# shield.net
KiCad netlist of a schematic drawn in EAGLE
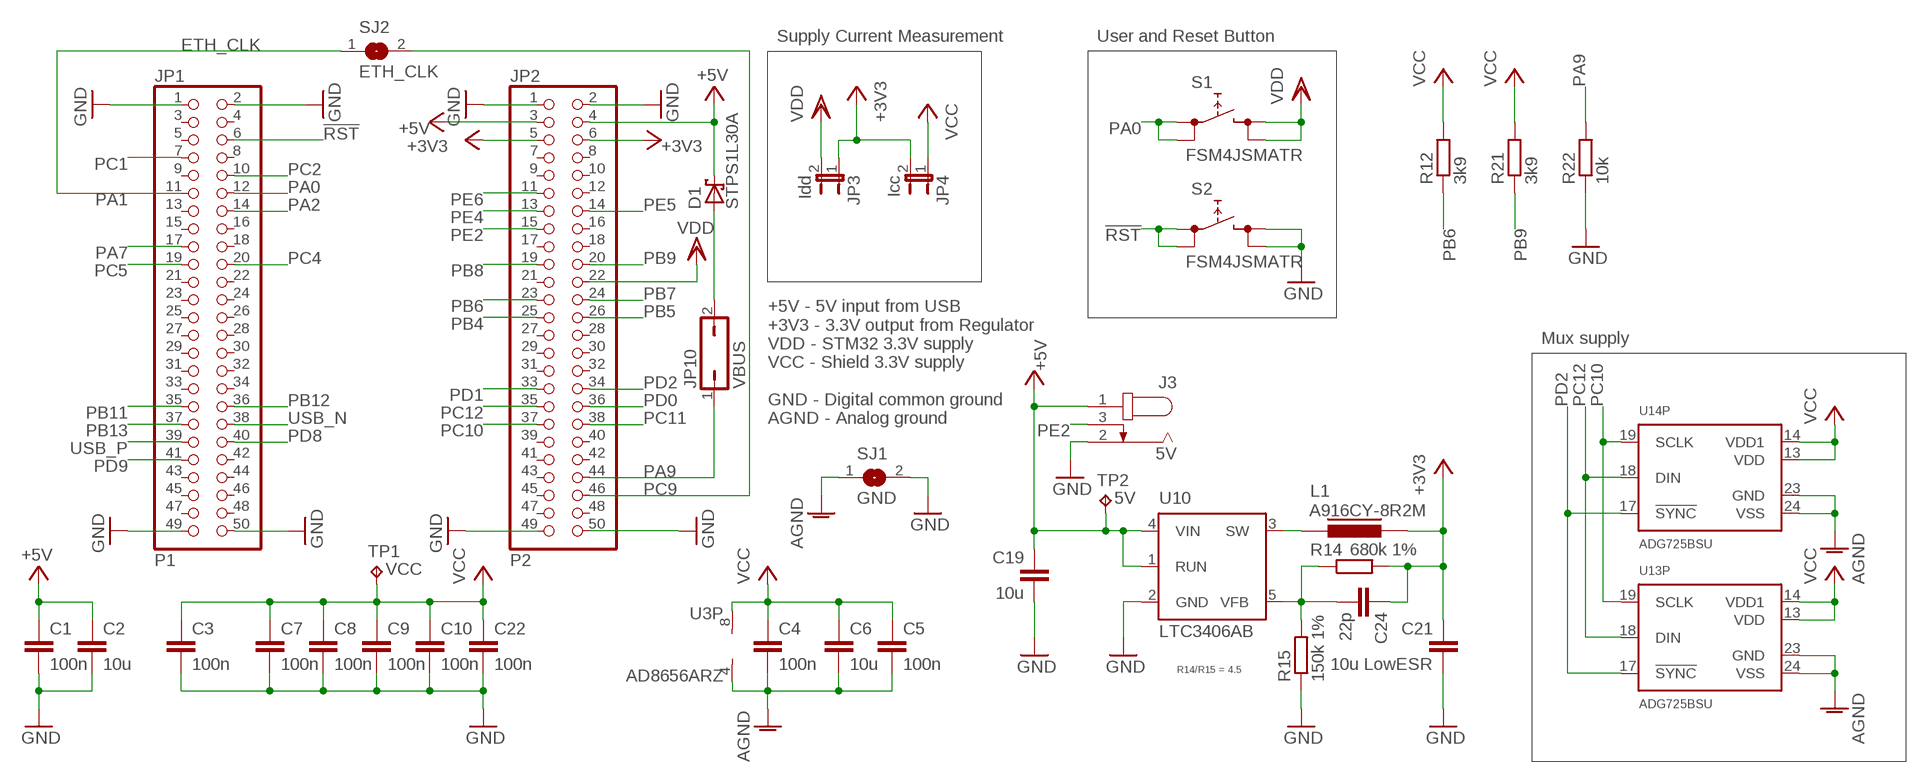
[diagram p0: schematic, sheet 1]
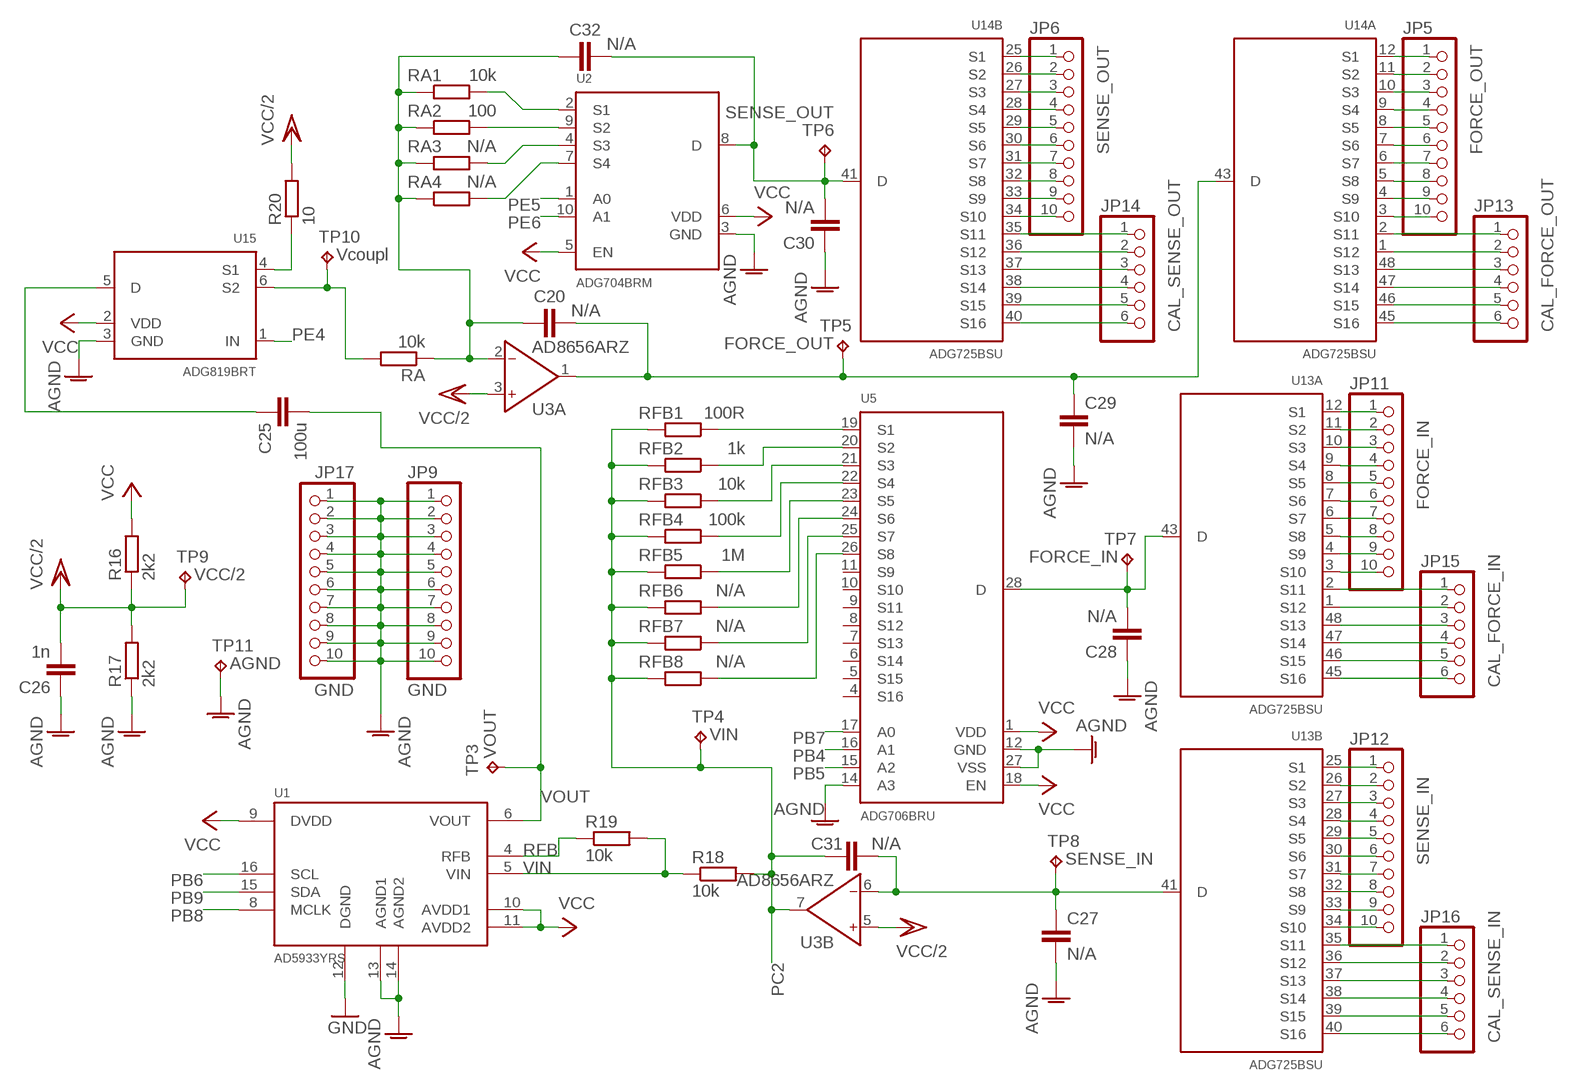
[diagram p1: schematic, sheet 2]
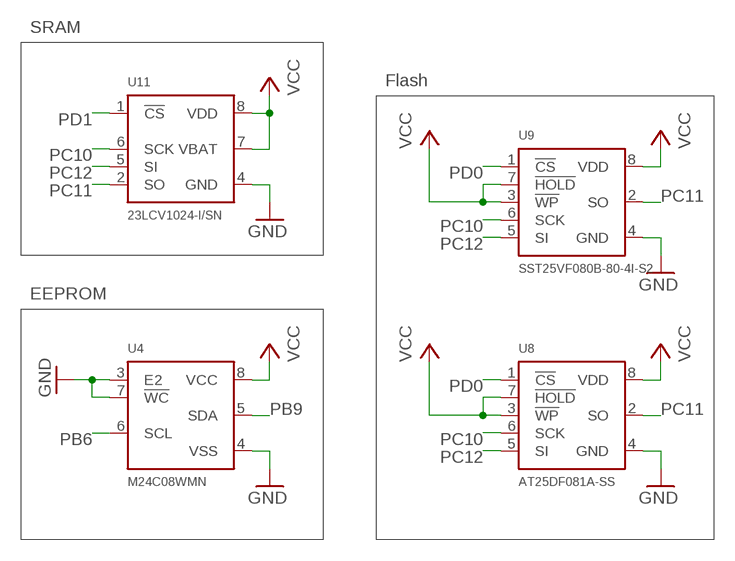
[diagram p2: schematic, sheet 3]
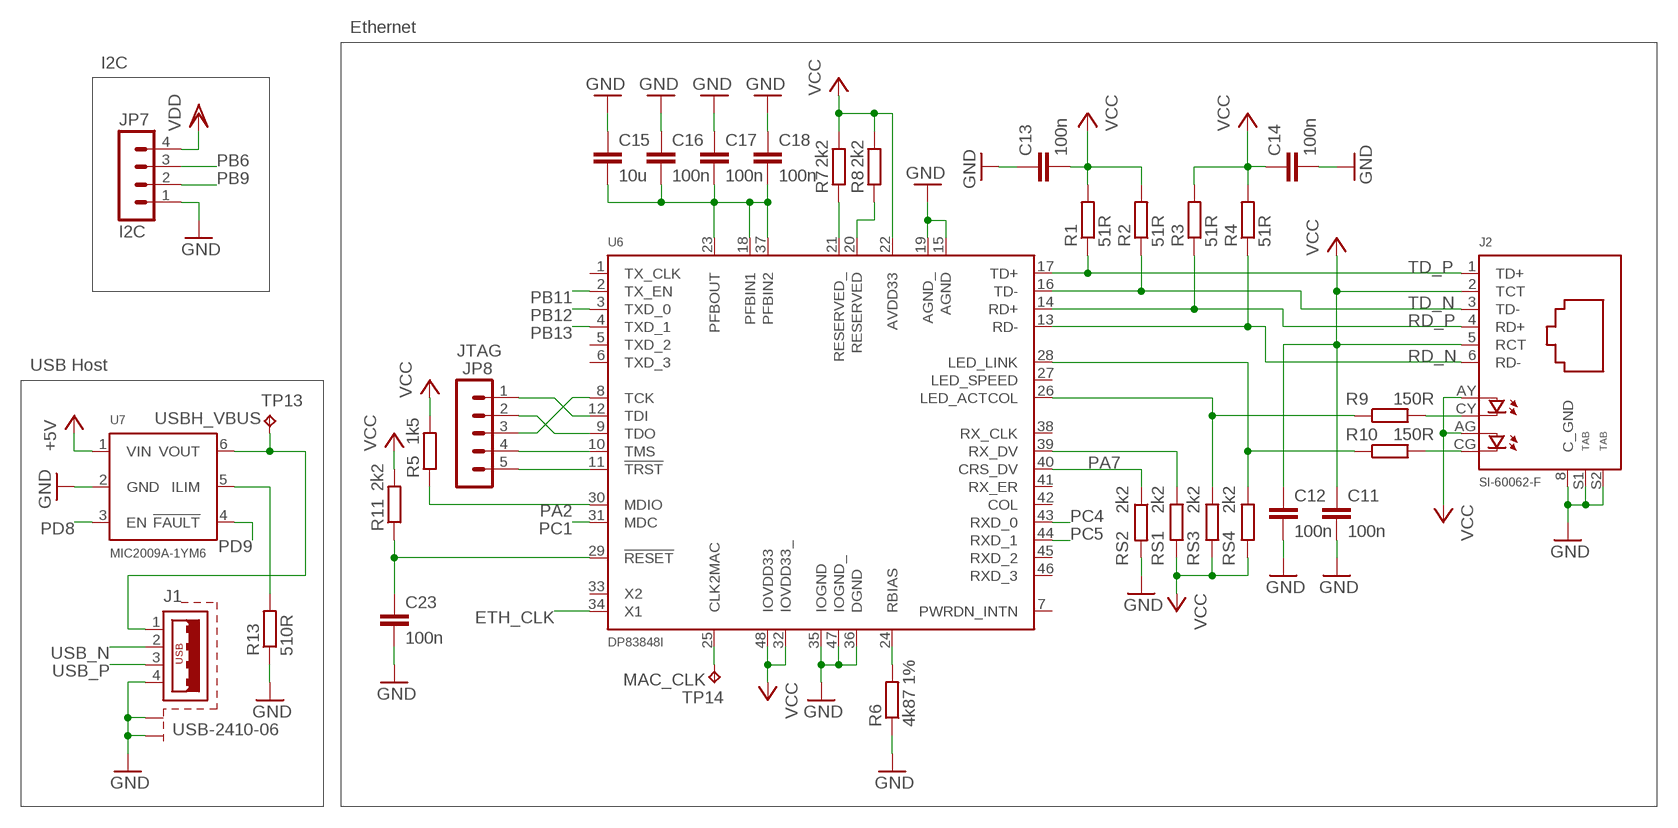
[diagram p3: schematic, sheet 4]

(export (version "E")
  (design (tool "Eeschema 10.0.6"))
  (components
    (comp (ref "U4")
      (value "M24C08WMN")
      (footprint "eagle-import:SO8")
      (libsource (lib "eagle-import") (part "M24C08MNW"))
    )
    (comp (ref "U8")
      (value "AT25DF081A-SS")
      (footprint "eagle-import:SO8")
      (libsource (lib "eagle-import") (part "AT25DF081A-SS"))
    )
    (comp (ref "U9")
      (value "SST25VF080B-80-4I-S2")
      (footprint "eagle-import:SOIC8")
      (libsource (lib "eagle-import") (part "SST25VF080B-S2-80-4I"))
    )
    (comp (ref "U11")
      (value "23LCV1024-I/SN")
      (footprint "eagle-import:SO8")
      (libsource (lib "eagle-import") (part "23LCV1024/SN-I"))
    )
    (comp (ref "C11")
      (value "100n")
      (footprint "eagle-import:C0603")
      (libsource (lib "eagle-import") (part "C-EUC0603"))
    )
    (comp (ref "C12")
      (value "100n")
      (footprint "eagle-import:C0603")
      (libsource (lib "eagle-import") (part "C-EUC0603"))
    )
    (comp (ref "C13")
      (value "100n")
      (footprint "eagle-import:C0603")
      (libsource (lib "eagle-import") (part "C-EUC0603"))
    )
    (comp (ref "C14")
      (value "100n")
      (footprint "eagle-import:C0603")
      (libsource (lib "eagle-import") (part "C-EUC0603"))
    )
    (comp (ref "C15")
      (value "10u")
      (footprint "eagle-import:C0603")
      (libsource (lib "eagle-import") (part "C-EUC0603"))
    )
    (comp (ref "C16")
      (value "100n")
      (footprint "eagle-import:C0603")
      (libsource (lib "eagle-import") (part "C-EUC0603"))
    )
    (comp (ref "C17")
      (value "100n")
      (footprint "eagle-import:C0603")
      (libsource (lib "eagle-import") (part "C-EUC0603"))
    )
    (comp (ref "C18")
      (value "100n")
      (footprint "eagle-import:C0603")
      (libsource (lib "eagle-import") (part "C-EUC0603"))
    )
    (comp (ref "C23")
      (value "100n")
      (footprint "eagle-import:C0603")
      (libsource (lib "eagle-import") (part "C-EUC0603"))
    )
    (comp (ref "J1")
      (value "USB-2410-06")
      (footprint "eagle-import:USB-2410-06")
      (libsource (lib "eagle-import") (part "USB-2410-06"))
    )
    (comp (ref "J2")
      (value "SI-60062-F")
      (footprint "eagle-import:SI-60062-F")
      (libsource (lib "eagle-import") (part "SI-60062-F"))
    )
    (comp (ref "JP7")
      (value "I2C")
      (footprint "eagle-import:MA04-1")
      (libsource (lib "eagle-import") (part "MA04-1"))
    )
    (comp (ref "JP8")
      (value "JTAG")
      (footprint "eagle-import:MA05-1")
      (libsource (lib "eagle-import") (part "MA05-1"))
    )
    (comp (ref "R1")
      (value "51R")
      (footprint "eagle-import:R0603")
      (libsource (lib "eagle-import") (part "R-EU_R0603"))
    )
    (comp (ref "R2")
      (value "51R")
      (footprint "eagle-import:R0603")
      (libsource (lib "eagle-import") (part "R-EU_R0603"))
    )
    (comp (ref "R3")
      (value "51R")
      (footprint "eagle-import:R0603")
      (libsource (lib "eagle-import") (part "R-EU_R0603"))
    )
    (comp (ref "R4")
      (value "51R")
      (footprint "eagle-import:R0603")
      (libsource (lib "eagle-import") (part "R-EU_R0603"))
    )
    (comp (ref "R5")
      (value "1k5")
      (footprint "eagle-import:R0603")
      (libsource (lib "eagle-import") (part "R-EU_R0603"))
    )
    (comp (ref "R6")
      (value "4k87 1%")
      (footprint "eagle-import:R0603")
      (libsource (lib "eagle-import") (part "R-EU_R0603"))
    )
    (comp (ref "R7")
      (value "2k2")
      (footprint "eagle-import:R0603")
      (libsource (lib "eagle-import") (part "R-EU_R0603"))
    )
    (comp (ref "R8")
      (value "2k2")
      (footprint "eagle-import:R0603")
      (libsource (lib "eagle-import") (part "R-EU_R0603"))
    )
    (comp (ref "R9")
      (value "150R")
      (footprint "eagle-import:R0603")
      (libsource (lib "eagle-import") (part "R-EU_R0603"))
    )
    (comp (ref "R10")
      (value "150R")
      (footprint "eagle-import:R0603")
      (libsource (lib "eagle-import") (part "R-EU_R0603"))
    )
    (comp (ref "R11")
      (value "2k2")
      (footprint "eagle-import:R0603")
      (libsource (lib "eagle-import") (part "R-EU_R0603"))
    )
    (comp (ref "R13")
      (value "510R")
      (footprint "eagle-import:R0603")
      (libsource (lib "eagle-import") (part "R-EU_R0603"))
    )
    (comp (ref "RS1")
      (value "2k2")
      (footprint "eagle-import:R0603")
      (libsource (lib "eagle-import") (part "R-EU_R0603"))
    )
    (comp (ref "RS2")
      (value "2k2")
      (footprint "eagle-import:R0603")
      (libsource (lib "eagle-import") (part "R-EU_R0603"))
    )
    (comp (ref "RS3")
      (value "2k2")
      (footprint "eagle-import:R0603")
      (libsource (lib "eagle-import") (part "R-EU_R0603"))
    )
    (comp (ref "RS4")
      (value "2k2")
      (footprint "eagle-import:R0603")
      (libsource (lib "eagle-import") (part "R-EU_R0603"))
    )
    (comp (ref "TP13")
      (value "TPTP20R")
      (footprint "eagle-import:TP20R")
      (fields (field (name "TP_SIGNAL_NAME") "USBH_VBUS"))
      (libsource (lib "eagle-import") (part "TPTP20R"))
    )
    (comp (ref "TP14")
      (value "TPTP20R")
      (footprint "eagle-import:TP20R")
      (fields (field (name "TP_SIGNAL_NAME") "MAC_CLK"))
      (libsource (lib "eagle-import") (part "TPTP20R"))
    )
    (comp (ref "U6")
      (value "DP83848I")
      (footprint "eagle-import:LQFP48")
      (fields (field (name "MPN") "DP83848IVV"))
      (libsource (lib "eagle-import") (part "DP83848I"))
    )
    (comp (ref "U7")
      (value "MIC2009A-1YM6")
      (footprint "eagle-import:SOT23-6")
      (libsource (lib "eagle-import") (part "MIC2009A-1YM6"))
    )
    (comp (ref "C20")
      (value "N/A")
      (footprint "eagle-import:C0603")
      (libsource (lib "eagle-import") (part "C-EUC0603"))
    )
    (comp (ref "C25")
      (value "100u")
      (footprint "eagle-import:C1206")
      (libsource (lib "eagle-import") (part "C-EUC1206"))
    )
    (comp (ref "C26")
      (value "1n")
      (footprint "eagle-import:C0603")
      (libsource (lib "eagle-import") (part "C-EUC0603"))
    )
    (comp (ref "C27")
      (value "N/A")
      (footprint "eagle-import:C0805")
      (libsource (lib "eagle-import") (part "C-EUC0805"))
    )
    (comp (ref "C28")
      (value "N/A")
      (footprint "eagle-import:C0805")
      (libsource (lib "eagle-import") (part "C-EUC0805"))
    )
    (comp (ref "C29")
      (value "N/A")
      (footprint "eagle-import:C0805")
      (libsource (lib "eagle-import") (part "C-EUC0805"))
    )
    (comp (ref "C30")
      (value "N/A")
      (footprint "eagle-import:C0805")
      (libsource (lib "eagle-import") (part "C-EUC0805"))
    )
    (comp (ref "C31")
      (value "N/A")
      (footprint "eagle-import:C0603")
      (libsource (lib "eagle-import") (part "C-EUC0603"))
    )
    (comp (ref "C32")
      (value "N/A")
      (footprint "eagle-import:C0603")
      (libsource (lib "eagle-import") (part "C-EUC0603"))
    )
    (comp (ref "JP5")
      (value "FORCE_OUT")
      (footprint "eagle-import:1X10")
      (libsource (lib "eagle-import") (part "PINHD-1X10"))
    )
    (comp (ref "JP6")
      (value "SENSE_OUT")
      (footprint "eagle-import:1X10")
      (libsource (lib "eagle-import") (part "PINHD-1X10"))
    )
    (comp (ref "JP9")
      (value "GND")
      (footprint "eagle-import:1X10")
      (libsource (lib "eagle-import") (part "PINHD-1X10"))
    )
    (comp (ref "JP11")
      (value "FORCE_IN")
      (footprint "eagle-import:1X10")
      (libsource (lib "eagle-import") (part "PINHD-1X10"))
    )
    (comp (ref "JP12")
      (value "SENSE_IN")
      (footprint "eagle-import:1X10")
      (libsource (lib "eagle-import") (part "PINHD-1X10"))
    )
    (comp (ref "JP13")
      (value "CAL_FORCE_OUT")
      (footprint "eagle-import:1X06")
      (libsource (lib "eagle-import") (part "PINHD-1X6"))
    )
    (comp (ref "JP14")
      (value "CAL_SENSE_OUT")
      (footprint "eagle-import:1X06")
      (libsource (lib "eagle-import") (part "PINHD-1X6"))
    )
    (comp (ref "JP15")
      (value "CAL_FORCE_IN")
      (footprint "eagle-import:1X06")
      (libsource (lib "eagle-import") (part "PINHD-1X6"))
    )
    (comp (ref "JP16")
      (value "CAL_SENSE_IN")
      (footprint "eagle-import:1X06")
      (libsource (lib "eagle-import") (part "PINHD-1X6"))
    )
    (comp (ref "JP17")
      (value "GND")
      (footprint "eagle-import:1X10")
      (libsource (lib "eagle-import") (part "PINHD-1X10"))
    )
    (comp (ref "R16")
      (value "2k2")
      (footprint "eagle-import:R0603")
      (libsource (lib "eagle-import") (part "R-EU_R0603"))
    )
    (comp (ref "R17")
      (value "2k2")
      (footprint "eagle-import:R0603")
      (libsource (lib "eagle-import") (part "R-EU_R0603"))
    )
    (comp (ref "R18")
      (value "10k")
      (footprint "eagle-import:R0603")
      (libsource (lib "eagle-import") (part "R-EU_R0603"))
    )
    (comp (ref "R19")
      (value "10k")
      (footprint "eagle-import:R0603")
      (libsource (lib "eagle-import") (part "R-EU_R0603"))
    )
    (comp (ref "R20")
      (value "10")
      (footprint "eagle-import:R0603")
      (libsource (lib "eagle-import") (part "R-EU_R0603"))
    )
    (comp (ref "RA")
      (value "10k")
      (footprint "eagle-import:R0603")
      (libsource (lib "eagle-import") (part "R-EU_R0603"))
    )
    (comp (ref "RA1")
      (value "10k")
      (footprint "eagle-import:R0603")
      (libsource (lib "eagle-import") (part "R-EU_R0603"))
    )
    (comp (ref "RA2")
      (value "100")
      (footprint "eagle-import:R0603")
      (libsource (lib "eagle-import") (part "R-EU_R0603"))
    )
    (comp (ref "RA3")
      (value "N/A")
      (footprint "eagle-import:R0603")
      (libsource (lib "eagle-import") (part "R-EU_R0603"))
    )
    (comp (ref "RA4")
      (value "N/A")
      (footprint "eagle-import:R0603")
      (libsource (lib "eagle-import") (part "R-EU_R0603"))
    )
    (comp (ref "RFB1")
      (value "100R")
      (footprint "eagle-import:R0603")
      (libsource (lib "eagle-import") (part "R-EU_R0603"))
    )
    (comp (ref "RFB2")
      (value "1k")
      (footprint "eagle-import:R0603")
      (libsource (lib "eagle-import") (part "R-EU_R0603"))
    )
    (comp (ref "RFB3")
      (value "10k")
      (footprint "eagle-import:R0603")
      (libsource (lib "eagle-import") (part "R-EU_R0603"))
    )
    (comp (ref "RFB4")
      (value "100k")
      (footprint "eagle-import:R0603")
      (libsource (lib "eagle-import") (part "R-EU_R0603"))
    )
    (comp (ref "RFB5")
      (value "1M")
      (footprint "eagle-import:R0603")
      (libsource (lib "eagle-import") (part "R-EU_R0603"))
    )
    (comp (ref "RFB6")
      (value "N/A")
      (footprint "eagle-import:R0603")
      (libsource (lib "eagle-import") (part "R-EU_R0603"))
    )
    (comp (ref "RFB7")
      (value "N/A")
      (footprint "eagle-import:R0603")
      (libsource (lib "eagle-import") (part "R-EU_R0603"))
    )
    (comp (ref "RFB8")
      (value "N/A")
      (footprint "eagle-import:R0603")
      (libsource (lib "eagle-import") (part "R-EU_R0603"))
    )
    (comp (ref "TP3")
      (value "TPTP20R")
      (footprint "eagle-import:TP20R")
      (fields (field (name "TP_SIGNAL_NAME") "VOUT"))
      (libsource (lib "eagle-import") (part "TPTP20R"))
    )
    (comp (ref "TP4")
      (value "TPTP20R")
      (footprint "eagle-import:TP20R")
      (fields (field (name "TP_SIGNAL_NAME") "VIN"))
      (libsource (lib "eagle-import") (part "TPTP20R"))
    )
    (comp (ref "TP5")
      (value "TPTP20R")
      (footprint "eagle-import:TP20R")
      (fields (field (name "TP_SIGNAL_NAME") "FORCE_OUT"))
      (libsource (lib "eagle-import") (part "TPTP20R"))
    )
    (comp (ref "TP6")
      (value "TPTP20R")
      (footprint "eagle-import:TP20R")
      (fields (field (name "TP_SIGNAL_NAME") "SENSE_OUT"))
      (libsource (lib "eagle-import") (part "TPTP20R"))
    )
    (comp (ref "TP7")
      (value "TPTP20R")
      (footprint "eagle-import:TP20R")
      (fields (field (name "TP_SIGNAL_NAME") "FORCE_IN"))
      (libsource (lib "eagle-import") (part "TPTP20R"))
    )
    (comp (ref "TP8")
      (value "TPTP20R")
      (footprint "eagle-import:TP20R")
      (fields (field (name "TP_SIGNAL_NAME") "SENSE_IN"))
      (libsource (lib "eagle-import") (part "TPTP20R"))
    )
    (comp (ref "TP9")
      (value "TPTP20R")
      (footprint "eagle-import:TP20R")
      (fields (field (name "TP_SIGNAL_NAME") "VCC/2"))
      (libsource (lib "eagle-import") (part "TPTP20R"))
    )
    (comp (ref "TP10")
      (value "TPTP20R")
      (footprint "eagle-import:TP20R")
      (fields (field (name "TP_SIGNAL_NAME") "Vcoupl"))
      (libsource (lib "eagle-import") (part "TPTP20R"))
    )
    (comp (ref "TP11")
      (value "TPPAD1-13")
      (footprint "eagle-import:P1-13")
      (fields (field (name "TP_SIGNAL_NAME") "AGND"))
      (libsource (lib "eagle-import") (part "TPPAD1-13"))
    )
    (comp (ref "U1")
      (value "AD5933YRS")
      (footprint "eagle-import:SSOP16")
      (libsource (lib "eagle-import") (part "AD5933RSY"))
    )
    (comp (ref "U2")
      (value "ADG704BRM")
      (footprint "eagle-import:MSOP10")
      (libsource (lib "eagle-import") (part "ADG704RMB"))
    )
    (comp (ref "U3")
      (value "AD8656ARZ")
      (footprint "eagle-import:SOIC8")
      (libsource (lib "eagle-import") (part "AD8656ZAR"))
    )
    (comp (ref "U5")
      (value "ADG706BRU")
      (footprint "eagle-import:TSSOP28")
      (libsource (lib "eagle-import") (part "ADG706RUB"))
    )
    (comp (ref "U13")
      (value "ADG725BSU")
      (footprint "eagle-import:TQFP48")
      (libsource (lib "eagle-import") (part "ADG725SUB"))
    )
    (comp (ref "U14")
      (value "ADG725BSU")
      (footprint "eagle-import:TQFP48")
      (libsource (lib "eagle-import") (part "ADG725SUB"))
    )
    (comp (ref "U15")
      (value "ADG819BRT")
      (footprint "eagle-import:SOT23-6")
      (libsource (lib "eagle-import") (part "ADG819RTB"))
    )
    (comp (ref "C1")
      (value "100n")
      (footprint "eagle-import:C0603")
      (libsource (lib "eagle-import") (part "C-EUC0603"))
    )
    (comp (ref "C2")
      (value "10u")
      (footprint "eagle-import:C0603")
      (libsource (lib "eagle-import") (part "C-EUC0603"))
    )
    (comp (ref "C3")
      (value "100n")
      (footprint "eagle-import:C0603")
      (libsource (lib "eagle-import") (part "C-EUC0603"))
    )
    (comp (ref "C4")
      (value "100n")
      (footprint "eagle-import:C0603")
      (libsource (lib "eagle-import") (part "C-EUC0603"))
    )
    (comp (ref "C5")
      (value "100n")
      (footprint "eagle-import:C0603")
      (libsource (lib "eagle-import") (part "C-EUC0603"))
    )
    (comp (ref "C6")
      (value "10u")
      (footprint "eagle-import:C0603")
      (libsource (lib "eagle-import") (part "C-EUC0603"))
    )
    (comp (ref "C7")
      (value "100n")
      (footprint "eagle-import:C0603")
      (libsource (lib "eagle-import") (part "C-EUC0603"))
    )
    (comp (ref "C8")
      (value "100n")
      (footprint "eagle-import:C0603")
      (libsource (lib "eagle-import") (part "C-EUC0603"))
    )
    (comp (ref "C9")
      (value "100n")
      (footprint "eagle-import:C0603")
      (libsource (lib "eagle-import") (part "C-EUC0603"))
    )
    (comp (ref "C10")
      (value "100n")
      (footprint "eagle-import:C0603")
      (libsource (lib "eagle-import") (part "C-EUC0603"))
    )
    (comp (ref "C19")
      (value "10u")
      (footprint "eagle-import:C3216")
      (libsource (lib "eagle-import") (part "C-EUC3216"))
    )
    (comp (ref "C21")
      (value "10u LowESR")
      (footprint "eagle-import:C3216")
      (libsource (lib "eagle-import") (part "C-EUC3216"))
    )
    (comp (ref "C22")
      (value "100n")
      (footprint "eagle-import:C0603")
      (libsource (lib "eagle-import") (part "C-EUC0603"))
    )
    (comp (ref "C24")
      (value "22p")
      (footprint "eagle-import:C0603")
      (libsource (lib "eagle-import") (part "C-EUC0603"))
    )
    (comp (ref "D1")
      (value "STPS1L30A")
      (footprint "eagle-import:DO214AC")
      (libsource (lib "eagle-import") (part "STPS1L30A"))
    )
    (comp (ref "J3")
      (value "5V")
      (footprint "eagle-import:JACK-SMD2.5")
      (libsource (lib "eagle-import") (part "JACK-PLUG-S2.5"))
    )
    (comp (ref "JP1")
      (value "P1")
      (footprint "eagle-import:2X25-F")
      (libsource (lib "eagle-import") (part "PINHD-2X25-F"))
    )
    (comp (ref "JP2")
      (value "P2")
      (footprint "eagle-import:2X25-F")
      (libsource (lib "eagle-import") (part "PINHD-2X25-F"))
    )
    (comp (ref "JP3")
      (value "Idd")
      (footprint "eagle-import:JP1")
      (libsource (lib "eagle-import") (part "JP1E"))
    )
    (comp (ref "JP4")
      (value "Icc")
      (footprint "eagle-import:JP1")
      (libsource (lib "eagle-import") (part "JP1E"))
    )
    (comp (ref "JP10")
      (value "VBUS")
      (footprint "eagle-import:JP1")
      (libsource (lib "eagle-import") (part "JP1Q"))
    )
    (comp (ref "L1")
      (value "A916CY-8R2M")
      (footprint "eagle-import:D63CB")
      (libsource (lib "eagle-import") (part "A916CY-8R2M"))
    )
    (comp (ref "R12")
      (value "3k9")
      (footprint "eagle-import:R0603")
      (libsource (lib "eagle-import") (part "R-EU_R0603"))
    )
    (comp (ref "R14")
      (value "680k 1%")
      (footprint "eagle-import:R0603")
      (libsource (lib "eagle-import") (part "R-EU_R0603"))
    )
    (comp (ref "R15")
      (value "150k 1%")
      (footprint "eagle-import:R0603")
      (libsource (lib "eagle-import") (part "R-EU_R0603"))
    )
    (comp (ref "R21")
      (value "3k9")
      (footprint "eagle-import:R0603")
      (libsource (lib "eagle-import") (part "R-EU_R0603"))
    )
    (comp (ref "R22")
      (value "10k")
      (footprint "eagle-import:R0603")
      (libsource (lib "eagle-import") (part "R-EU_R0603"))
    )
    (comp (ref "S1")
      (value "FSM4JSMATR")
      (footprint "eagle-import:FSM")
      (libsource (lib "eagle-import") (part "FSM4JSMATR"))
    )
    (comp (ref "S2")
      (value "FSM4JSMATR")
      (footprint "eagle-import:FSM")
      (libsource (lib "eagle-import") (part "FSM4JSMATR"))
    )
    (comp (ref "SJ1")
      (value "GND")
      (footprint "eagle-import:SJ")
      (libsource (lib "eagle-import") (part "SJ"))
    )
    (comp (ref "SJ2")
      (value "ETH_CLK")
      (footprint "eagle-import:SJ")
      (libsource (lib "eagle-import") (part "SJ"))
    )
    (comp (ref "TP1")
      (value "TPTP20R")
      (footprint "eagle-import:TP20R")
      (fields (field (name "TP_SIGNAL_NAME") "VCC"))
      (libsource (lib "eagle-import") (part "TPTP20R"))
    )
    (comp (ref "TP2")
      (value "TPTP20R")
      (footprint "eagle-import:TP20R")
      (fields (field (name "TP_SIGNAL_NAME") "5V"))
      (libsource (lib "eagle-import") (part "TPTP20R"))
    )
    (comp (ref "U10")
      (value "LTC3406AB")
      (footprint "eagle-import:TSOT23-5")
      (libsource (lib "eagle-import") (part "LTC3406AB"))
    )
  )
  (nets
    (net (code "1") (name "+3V3") (class "Default")
      (node (ref "C21") (pin "1") (pinfunction "1_1") (pintype "passive"))
      (node (ref "C24") (pin "1") (pinfunction "1_1") (pintype "passive"))
      (node (ref "JP2") (pin "5") (pinfunction "5_5") (pintype "passive"))
      (node (ref "JP2") (pin "6") (pinfunction "6_6") (pintype "passive"))
      (node (ref "JP3") (pin "1") (pinfunction "1_1") (pintype "passive"))
      (node (ref "JP4") (pin "2") (pinfunction "2_2") (pintype "passive"))
      (node (ref "L1") (pin "2") (pinfunction "2_2") (pintype "passive"))
      (node (ref "R14") (pin "2") (pinfunction "2_2") (pintype "passive"))
    )
    (net (code "2") (name "+5V") (class "Default")
      (node (ref "C1") (pin "1") (pinfunction "1_1") (pintype "passive"))
      (node (ref "C19") (pin "1") (pinfunction "1_1") (pintype "passive"))
      (node (ref "C2") (pin "1") (pinfunction "1_1") (pintype "passive"))
      (node (ref "D1") (pin "C") (pinfunction "C_C") (pintype "passive"))
      (node (ref "J3") (pin "1") (pinfunction "1_1") (pintype "passive"))
      (node (ref "JP2") (pin "3") (pinfunction "3_3") (pintype "passive"))
      (node (ref "JP2") (pin "4") (pinfunction "4_4") (pintype "passive"))
      (node (ref "TP2") (pin "TP") (pinfunction "TP_TP") (pintype "input"))
      (node (ref "U10") (pin "1") (pinfunction "RUN_1") (pintype "input"))
      (node (ref "U10") (pin "4") (pinfunction "VIN_4") (pintype "power_in"))
      (node (ref "U7") (pin "1") (pinfunction "VIN_1") (pintype "power_in"))
    )
    (net (code "3") (name "AGND") (class "Default")
      (node (ref "C26") (pin "1") (pinfunction "1_1") (pintype "passive"))
      (node (ref "C27") (pin "2") (pinfunction "2_2") (pintype "passive"))
      (node (ref "C28") (pin "1") (pinfunction "1_1") (pintype "passive"))
      (node (ref "C29") (pin "2") (pinfunction "2_2") (pintype "passive"))
      (node (ref "C30") (pin "1") (pinfunction "1_1") (pintype "passive"))
      (node (ref "C4") (pin "2") (pinfunction "2_2") (pintype "passive"))
      (node (ref "C5") (pin "2") (pinfunction "2_2") (pintype "passive"))
      (node (ref "C6") (pin "2") (pinfunction "2_2") (pintype "passive"))
      (node (ref "JP17") (pin "1") (pinfunction "1_1") (pintype "passive"))
      (node (ref "JP17") (pin "10") (pinfunction "10_10") (pintype "passive"))
      (node (ref "JP17") (pin "2") (pinfunction "2_2") (pintype "passive"))
      (node (ref "JP17") (pin "3") (pinfunction "3_3") (pintype "passive"))
      (node (ref "JP17") (pin "4") (pinfunction "4_4") (pintype "passive"))
      (node (ref "JP17") (pin "5") (pinfunction "5_5") (pintype "passive"))
      (node (ref "JP17") (pin "6") (pinfunction "6_6") (pintype "passive"))
      (node (ref "JP17") (pin "7") (pinfunction "7_7") (pintype "passive"))
      (node (ref "JP17") (pin "8") (pinfunction "8_8") (pintype "passive"))
      (node (ref "JP17") (pin "9") (pinfunction "9_9") (pintype "passive"))
      (node (ref "JP9") (pin "1") (pinfunction "1_1") (pintype "passive"))
      (node (ref "JP9") (pin "10") (pinfunction "10_10") (pintype "passive"))
      (node (ref "JP9") (pin "2") (pinfunction "2_2") (pintype "passive"))
      (node (ref "JP9") (pin "3") (pinfunction "3_3") (pintype "passive"))
      (node (ref "JP9") (pin "4") (pinfunction "4_4") (pintype "passive"))
      (node (ref "JP9") (pin "5") (pinfunction "5_5") (pintype "passive"))
      (node (ref "JP9") (pin "6") (pinfunction "6_6") (pintype "passive"))
      (node (ref "JP9") (pin "7") (pinfunction "7_7") (pintype "passive"))
      (node (ref "JP9") (pin "8") (pinfunction "8_8") (pintype "passive"))
      (node (ref "JP9") (pin "9") (pinfunction "9_9") (pintype "passive"))
      (node (ref "R17") (pin "1") (pinfunction "1_1") (pintype "passive"))
      (node (ref "SJ1") (pin "1") (pinfunction "1_1") (pintype "passive"))
      (node (ref "TP11") (pin "TP") (pinfunction "TP_TP") (pintype "input"))
      (node (ref "U1") (pin "13") (pinfunction "AGND1_13") (pintype "bidirectional"))
      (node (ref "U1") (pin "14") (pinfunction "AGND2_14") (pintype "bidirectional"))
      (node (ref "U13") (pin "23") (pinfunction "GND_23") (pintype "power_in"))
      (node (ref "U13") (pin "24") (pinfunction "VSS_24") (pintype "power_in"))
      (node (ref "U14") (pin "23") (pinfunction "GND_23") (pintype "power_in"))
      (node (ref "U14") (pin "24") (pinfunction "VSS_24") (pintype "power_in"))
      (node (ref "U15") (pin "3") (pinfunction "GND_3") (pintype "power_in"))
      (node (ref "U2") (pin "3") (pinfunction "GND_3") (pintype "power_in"))
      (node (ref "U3") (pin "4") (pinfunction "V-_4") (pintype "power_in"))
      (node (ref "U5") (pin "12") (pinfunction "GND_12") (pintype "power_in"))
      (node (ref "U5") (pin "14") (pinfunction "A3_14") (pintype "input"))
      (node (ref "U5") (pin "27") (pinfunction "VSS_27") (pintype "power_in"))
    )
    (net (code "4") (name "ETH_CLK") (class "Default")
      (node (ref "JP1") (pin "11") (pinfunction "11_11") (pintype "passive"))
      (node (ref "SJ2") (pin "1") (pinfunction "1_1") (pintype "passive"))
      (node (ref "U6") (pin "34") (pinfunction "X1_34") (pintype "input"))
    )
    (net (code "5") (name "GND") (class "Default")
      (node (ref "C1") (pin "2") (pinfunction "2_2") (pintype "passive"))
      (node (ref "C10") (pin "2") (pinfunction "2_2") (pintype "passive"))
      (node (ref "C11") (pin "2") (pinfunction "2_2") (pintype "passive"))
      (node (ref "C12") (pin "2") (pinfunction "2_2") (pintype "passive"))
      (node (ref "C13") (pin "1") (pinfunction "1_1") (pintype "passive"))
      (node (ref "C14") (pin "2") (pinfunction "2_2") (pintype "passive"))
      (node (ref "C15") (pin "1") (pinfunction "1_1") (pintype "passive"))
      (node (ref "C16") (pin "1") (pinfunction "1_1") (pintype "passive"))
      (node (ref "C17") (pin "1") (pinfunction "1_1") (pintype "passive"))
      (node (ref "C18") (pin "1") (pinfunction "1_1") (pintype "passive"))
      (node (ref "C19") (pin "2") (pinfunction "2_2") (pintype "passive"))
      (node (ref "C2") (pin "2") (pinfunction "2_2") (pintype "passive"))
      (node (ref "C21") (pin "2") (pinfunction "2_2") (pintype "passive"))
      (node (ref "C22") (pin "2") (pinfunction "2_2") (pintype "passive"))
      (node (ref "C23") (pin "2") (pinfunction "2_2") (pintype "passive"))
      (node (ref "C3") (pin "2") (pinfunction "2_2") (pintype "passive"))
      (node (ref "C7") (pin "2") (pinfunction "2_2") (pintype "passive"))
      (node (ref "C8") (pin "2") (pinfunction "2_2") (pintype "passive"))
      (node (ref "C9") (pin "2") (pinfunction "2_2") (pintype "passive"))
      (node (ref "J1") (pin "4") (pinfunction "GND_4") (pintype "passive"))
      (node (ref "J1") (pin "S1") (pinfunction "S1_S1") (pintype "passive"))
      (node (ref "J1") (pin "S2") (pinfunction "S2_S2") (pintype "passive"))
      (node (ref "J2") (pin "8") (pinfunction "C_GND_8") (pintype "passive"))
      (node (ref "J2") (pin "S1") (pinfunction "TAB1_S1") (pintype "passive"))
      (node (ref "J2") (pin "S2") (pinfunction "TAB2_S2") (pintype "passive"))
      (node (ref "J3") (pin "2") (pinfunction "3_2") (pintype "passive"))
      (node (ref "JP1") (pin "1") (pinfunction "1_1") (pintype "passive"))
      (node (ref "JP1") (pin "2") (pinfunction "2_2") (pintype "passive"))
      (node (ref "JP1") (pin "49") (pinfunction "49_49") (pintype "passive"))
      (node (ref "JP1") (pin "50") (pinfunction "50_50") (pintype "passive"))
      (node (ref "JP2") (pin "1") (pinfunction "1_1") (pintype "passive"))
      (node (ref "JP2") (pin "2") (pinfunction "2_2") (pintype "passive"))
      (node (ref "JP2") (pin "49") (pinfunction "49_49") (pintype "passive"))
      (node (ref "JP2") (pin "50") (pinfunction "50_50") (pintype "passive"))
      (node (ref "JP7") (pin "1") (pinfunction "1_1") (pintype "passive"))
      (node (ref "R13") (pin "1") (pinfunction "1_1") (pintype "passive"))
      (node (ref "R15") (pin "1") (pinfunction "1_1") (pintype "passive"))
      (node (ref "R22") (pin "1") (pinfunction "1_1") (pintype "passive"))
      (node (ref "R6") (pin "1") (pinfunction "1_1") (pintype "passive"))
      (node (ref "RS2") (pin "2") (pinfunction "2_2") (pintype "passive"))
      (node (ref "S2") (pin "3") (pinfunction "1_3") (pintype "passive"))
      (node (ref "S2") (pin "4") (pinfunction "1_4") (pintype "passive"))
      (node (ref "SJ1") (pin "2") (pinfunction "2_2") (pintype "passive"))
      (node (ref "U1") (pin "12") (pinfunction "DGND_12") (pintype "bidirectional"))
      (node (ref "U10") (pin "2") (pinfunction "GND_2") (pintype "power_in"))
      (node (ref "U11") (pin "4") (pinfunction "GND_4") (pintype "power_in"))
      (node (ref "U4") (pin "3") (pinfunction "E2_3") (pintype "input"))
      (node (ref "U4") (pin "4") (pinfunction "VSS_4") (pintype "power_in"))
      (node (ref "U4") (pin "7") (pinfunction "~{WC}_7") (pintype "input"))
      (node (ref "U6") (pin "15") (pinfunction "AGND_15") (pintype "power_in"))
      (node (ref "U6") (pin "19") (pinfunction "AGND__19") (pintype "power_in"))
      (node (ref "U6") (pin "35") (pinfunction "IOGND_35") (pintype "power_in"))
      (node (ref "U6") (pin "36") (pinfunction "DGND_36") (pintype "power_in"))
      (node (ref "U6") (pin "47") (pinfunction "IOGND__47") (pintype "power_in"))
      (node (ref "U7") (pin "2") (pinfunction "GND_2") (pintype "power_in"))
      (node (ref "U8") (pin "4") (pinfunction "GND_4") (pintype "power_in"))
      (node (ref "U9") (pin "4") (pinfunction "GND_4") (pintype "power_in"))
    )
    (net (code "6") (name "Net-(D1-PadA)") (class "Default")
      (node (ref "D1") (pin "A") (pinfunction "A_A") (pintype "passive"))
      (node (ref "JP10") (pin "2") (pinfunction "2_2") (pintype "passive"))
    )
    (net (code "7") (name "Net-(J1-VCC)") (class "Default")
      (node (ref "J1") (pin "1") (pinfunction "VCC_1") (pintype "passive"))
      (node (ref "TP13") (pin "TP") (pinfunction "TP_TP") (pintype "input"))
      (node (ref "U7") (pin "6") (pinfunction "VOUT_6") (pintype "power_in"))
    )
    (net (code "8") (name "Net-(J2-PadCG)") (class "Default")
      (node (ref "J2") (pin "CG") (pinfunction "CG_CG") (pintype "passive"))
      (node (ref "R10") (pin "2") (pinfunction "2_2") (pintype "passive"))
    )
    (net (code "9") (name "Net-(J2-PadCY)") (class "Default")
      (node (ref "J2") (pin "CY") (pinfunction "CY_CY") (pintype "passive"))
      (node (ref "R9") (pin "2") (pinfunction "2_2") (pintype "passive"))
    )
    (net (code "10") (name "Net-(U2-S1)") (class "Default")
      (node (ref "RA1") (pin "2") (pinfunction "2_2") (pintype "passive"))
      (node (ref "U2") (pin "2") (pinfunction "S1_2") (pintype "bidirectional"))
    )
    (net (code "11") (name "Net-(U2-S2)") (class "Default")
      (node (ref "RA2") (pin "2") (pinfunction "2_2") (pintype "passive"))
      (node (ref "U2") (pin "9") (pinfunction "S2_9") (pintype "bidirectional"))
    )
    (net (code "12") (name "Net-(U2-S3)") (class "Default")
      (node (ref "RA3") (pin "2") (pinfunction "2_2") (pintype "passive"))
      (node (ref "U2") (pin "4") (pinfunction "S3_4") (pintype "bidirectional"))
    )
    (net (code "13") (name "Net-(U2-S4)") (class "Default")
      (node (ref "RA4") (pin "2") (pinfunction "2_2") (pintype "passive"))
      (node (ref "U2") (pin "7") (pinfunction "S4_7") (pintype "bidirectional"))
    )
    (net (code "14") (name "Net-(U3A-IN-)") (class "Default")
      (node (ref "C20") (pin "1") (pinfunction "1_1") (pintype "passive"))
      (node (ref "C32") (pin "1") (pinfunction "1_1") (pintype "passive"))
      (node (ref "RA") (pin "1") (pinfunction "1_1") (pintype "passive"))
      (node (ref "RA1") (pin "1") (pinfunction "1_1") (pintype "passive"))
      (node (ref "RA2") (pin "1") (pinfunction "1_1") (pintype "passive"))
      (node (ref "RA3") (pin "1") (pinfunction "1_1") (pintype "passive"))
      (node (ref "RA4") (pin "1") (pinfunction "1_1") (pintype "passive"))
      (node (ref "U3") (pin "2") (pinfunction "IN-_2") (pintype "input"))
    )
    (net (code "15") (name "Net-(U5-S1)") (class "Default")
      (node (ref "RFB1") (pin "1") (pinfunction "1_1") (pintype "passive"))
      (node (ref "U5") (pin "19") (pinfunction "S1_19") (pintype "bidirectional"))
    )
    (net (code "16") (name "Net-(U5-S2)") (class "Default")
      (node (ref "RFB2") (pin "1") (pinfunction "1_1") (pintype "passive"))
      (node (ref "U5") (pin "20") (pinfunction "S2_20") (pintype "bidirectional"))
    )
    (net (code "17") (name "Net-(U5-S3)") (class "Default")
      (node (ref "RFB3") (pin "1") (pinfunction "1_1") (pintype "passive"))
      (node (ref "U5") (pin "21") (pinfunction "S3_21") (pintype "bidirectional"))
    )
    (net (code "18") (name "Net-(U5-S4)") (class "Default")
      (node (ref "RFB4") (pin "1") (pinfunction "1_1") (pintype "passive"))
      (node (ref "U5") (pin "22") (pinfunction "S4_22") (pintype "bidirectional"))
    )
    (net (code "19") (name "Net-(U5-S5)") (class "Default")
      (node (ref "RFB5") (pin "1") (pinfunction "1_1") (pintype "passive"))
      (node (ref "U5") (pin "23") (pinfunction "S5_23") (pintype "bidirectional"))
    )
    (net (code "20") (name "Net-(U5-S6)") (class "Default")
      (node (ref "RFB6") (pin "1") (pinfunction "1_1") (pintype "passive"))
      (node (ref "U5") (pin "24") (pinfunction "S6_24") (pintype "bidirectional"))
    )
    (net (code "21") (name "Net-(U5-S7)") (class "Default")
      (node (ref "RFB7") (pin "1") (pinfunction "1_1") (pintype "passive"))
      (node (ref "U5") (pin "25") (pinfunction "S7_25") (pintype "bidirectional"))
    )
    (net (code "22") (name "Net-(U5-S8)") (class "Default")
      (node (ref "RFB8") (pin "1") (pinfunction "1_1") (pintype "passive"))
      (node (ref "U5") (pin "26") (pinfunction "S8_26") (pintype "bidirectional"))
    )
    (net (code "23") (name "Net-(U6-CLK2MAC)") (class "Default")
      (node (ref "TP14") (pin "TP") (pinfunction "TP_TP") (pintype "input"))
      (node (ref "U6") (pin "25") (pinfunction "CLK2MAC_25") (pintype "output"))
    )
    (net (code "24") (name "Net-(U6-LED_ACTCOL)") (class "Default")
      (node (ref "R9") (pin "1") (pinfunction "1_1") (pintype "passive"))
      (node (ref "RS3") (pin "2") (pinfunction "2_2") (pintype "passive"))
      (node (ref "U6") (pin "26") (pinfunction "LED_ACTCOL_26") (pintype "output"))
    )
    (net (code "25") (name "Net-(U6-LED_LINK)") (class "Default")
      (node (ref "R10") (pin "1") (pinfunction "1_1") (pintype "passive"))
      (node (ref "RS4") (pin "2") (pinfunction "2_2") (pintype "passive"))
      (node (ref "U6") (pin "28") (pinfunction "LED_LINK_28") (pintype "output"))
    )
    (net (code "26") (name "Net-(U6-PFBIN1)") (class "Default")
      (node (ref "C15") (pin "2") (pinfunction "2_2") (pintype "passive"))
      (node (ref "C16") (pin "2") (pinfunction "2_2") (pintype "passive"))
      (node (ref "C17") (pin "2") (pinfunction "2_2") (pintype "passive"))
      (node (ref "C18") (pin "2") (pinfunction "2_2") (pintype "passive"))
      (node (ref "U6") (pin "18") (pinfunction "PFBIN1_18") (pintype "input"))
      (node (ref "U6") (pin "23") (pinfunction "PFBOUT_23") (pintype "output"))
      (node (ref "U6") (pin "37") (pinfunction "PFBIN2_37") (pintype "input"))
    )
    (net (code "27") (name "Net-(U6-RBIAS)") (class "Default")
      (node (ref "R6") (pin "2") (pinfunction "2_2") (pintype "passive"))
      (node (ref "U6") (pin "24") (pinfunction "RBIAS_24") (pintype "bidirectional"))
    )
    (net (code "28") (name "Net-(U6-RESERVED)") (class "Default")
      (node (ref "R8") (pin "1") (pinfunction "1_1") (pintype "passive"))
      (node (ref "U6") (pin "20") (pinfunction "RESERVED_20") (pintype "input"))
    )
    (net (code "29") (name "Net-(U6-RESERVED_)") (class "Default")
      (node (ref "R7") (pin "1") (pinfunction "1_1") (pintype "passive"))
      (node (ref "U6") (pin "21") (pinfunction "RESERVED__21") (pintype "input"))
    )
    (net (code "30") (name "Net-(U6-RX_DV)") (class "Default")
      (node (ref "RS1") (pin "2") (pinfunction "2_2") (pintype "passive"))
      (node (ref "U6") (pin "39") (pinfunction "RX_DV_39") (pintype "output"))
    )
    (net (code "31") (name "Net-(U6-TCK)") (class "Default")
      (node (ref "JP8") (pin "3") (pinfunction "3_3") (pintype "passive"))
      (node (ref "U6") (pin "8") (pinfunction "TCK_8") (pintype "input"))
    )
    (net (code "32") (name "Net-(U6-TDI)") (class "Default")
      (node (ref "JP8") (pin "1") (pinfunction "1_1") (pintype "passive"))
      (node (ref "U6") (pin "12") (pinfunction "TDI_12") (pintype "input"))
    )
    (net (code "33") (name "Net-(U6-TDO)") (class "Default")
      (node (ref "JP8") (pin "2") (pinfunction "2_2") (pintype "passive"))
      (node (ref "U6") (pin "9") (pinfunction "TDO_9") (pintype "output"))
    )
    (net (code "34") (name "Net-(U6-TMS)") (class "Default")
      (node (ref "JP8") (pin "4") (pinfunction "4_4") (pintype "passive"))
      (node (ref "U6") (pin "10") (pinfunction "TMS_10") (pintype "input"))
    )
    (net (code "35") (name "Net-(U6-~{RESET})") (class "Default")
      (node (ref "C23") (pin "1") (pinfunction "1_1") (pintype "passive"))
      (node (ref "R11") (pin "1") (pinfunction "1_1") (pintype "passive"))
      (node (ref "U6") (pin "29") (pinfunction "~{RESET}_29") (pintype "input"))
    )
    (net (code "36") (name "Net-(U6-~{TRST})") (class "Default")
      (node (ref "JP8") (pin "5") (pinfunction "5_5") (pintype "passive"))
      (node (ref "U6") (pin "11") (pinfunction "~{TRST}_11") (pintype "input"))
    )
    (net (code "37") (name "Net-(U7-ILIM)") (class "Default")
      (node (ref "R13") (pin "2") (pinfunction "2_2") (pintype "passive"))
      (node (ref "U7") (pin "5") (pinfunction "ILIM_5") (pintype "passive"))
    )
    (net (code "38") (name "Net-(U10-SW)") (class "Default")
      (node (ref "L1") (pin "1") (pinfunction "1_1") (pintype "passive"))
      (node (ref "U10") (pin "3") (pinfunction "SW_3") (pintype "passive"))
    )
    (net (code "39") (name "Net-(U10-VFB)") (class "Default")
      (node (ref "C24") (pin "2") (pinfunction "2_2") (pintype "passive"))
      (node (ref "R14") (pin "1") (pinfunction "1_1") (pintype "passive"))
      (node (ref "R15") (pin "2") (pinfunction "2_2") (pintype "passive"))
      (node (ref "U10") (pin "5") (pinfunction "VFB_5") (pintype "input"))
    )
    (net (code "40") (name "Net-(U13A-D)") (class "Default")
      (node (ref "C28") (pin "2") (pinfunction "2_2") (pintype "passive"))
      (node (ref "TP7") (pin "TP") (pinfunction "TP_TP") (pintype "input"))
      (node (ref "U13") (pin "43") (pinfunction "D_43") (pintype "bidirectional"))
      (node (ref "U5") (pin "28") (pinfunction "D_28") (pintype "bidirectional"))
    )
    (net (code "41") (name "Net-(U13A-S1)") (class "Default")
      (node (ref "JP11") (pin "1") (pinfunction "1_1") (pintype "passive"))
      (node (ref "U13") (pin "12") (pinfunction "S1_12") (pintype "bidirectional"))
    )
    (net (code "42") (name "Net-(U13A-S2)") (class "Default")
      (node (ref "JP11") (pin "2") (pinfunction "2_2") (pintype "passive"))
      (node (ref "U13") (pin "11") (pinfunction "S2_11") (pintype "bidirectional"))
    )
    (net (code "43") (name "Net-(U13A-S3)") (class "Default")
      (node (ref "JP11") (pin "3") (pinfunction "3_3") (pintype "passive"))
      (node (ref "U13") (pin "10") (pinfunction "S3_10") (pintype "bidirectional"))
    )
    (net (code "44") (name "Net-(U13A-S4)") (class "Default")
      (node (ref "JP11") (pin "4") (pinfunction "4_4") (pintype "passive"))
      (node (ref "U13") (pin "9") (pinfunction "S4_9") (pintype "bidirectional"))
    )
    (net (code "45") (name "Net-(U13A-S5)") (class "Default")
      (node (ref "JP11") (pin "5") (pinfunction "5_5") (pintype "passive"))
      (node (ref "U13") (pin "8") (pinfunction "S5_8") (pintype "bidirectional"))
    )
    (net (code "46") (name "Net-(U13A-S6)") (class "Default")
      (node (ref "JP11") (pin "6") (pinfunction "6_6") (pintype "passive"))
      (node (ref "U13") (pin "7") (pinfunction "S6_7") (pintype "bidirectional"))
    )
    (net (code "47") (name "Net-(U13A-S7)") (class "Default")
      (node (ref "JP11") (pin "7") (pinfunction "7_7") (pintype "passive"))
      (node (ref "U13") (pin "6") (pinfunction "S7_6") (pintype "bidirectional"))
    )
    (net (code "48") (name "Net-(U13A-S8)") (class "Default")
      (node (ref "JP11") (pin "8") (pinfunction "8_8") (pintype "passive"))
      (node (ref "U13") (pin "5") (pinfunction "S8_5") (pintype "bidirectional"))
    )
    (net (code "49") (name "Net-(U13A-S9)") (class "Default")
      (node (ref "JP11") (pin "9") (pinfunction "9_9") (pintype "passive"))
      (node (ref "U13") (pin "4") (pinfunction "S9_4") (pintype "bidirectional"))
    )
    (net (code "50") (name "Net-(U13A-S10)") (class "Default")
      (node (ref "JP11") (pin "10") (pinfunction "10_10") (pintype "passive"))
      (node (ref "U13") (pin "3") (pinfunction "S10_3") (pintype "bidirectional"))
    )
    (net (code "51") (name "Net-(U13A-S11)") (class "Default")
      (node (ref "JP15") (pin "1") (pinfunction "1_1") (pintype "passive"))
      (node (ref "U13") (pin "2") (pinfunction "S11_2") (pintype "bidirectional"))
    )
    (net (code "52") (name "Net-(U13A-S12)") (class "Default")
      (node (ref "JP15") (pin "2") (pinfunction "2_2") (pintype "passive"))
      (node (ref "U13") (pin "1") (pinfunction "S12_1") (pintype "bidirectional"))
    )
    (net (code "53") (name "Net-(U13A-S13)") (class "Default")
      (node (ref "JP15") (pin "3") (pinfunction "3_3") (pintype "passive"))
      (node (ref "U13") (pin "48") (pinfunction "S13_48") (pintype "bidirectional"))
    )
    (net (code "54") (name "Net-(U13A-S14)") (class "Default")
      (node (ref "JP15") (pin "4") (pinfunction "4_4") (pintype "passive"))
      (node (ref "U13") (pin "47") (pinfunction "S14_47") (pintype "bidirectional"))
    )
    (net (code "55") (name "Net-(U13A-S15)") (class "Default")
      (node (ref "JP15") (pin "5") (pinfunction "5_5") (pintype "passive"))
      (node (ref "U13") (pin "46") (pinfunction "S15_46") (pintype "bidirectional"))
    )
    (net (code "56") (name "Net-(U13A-S16)") (class "Default")
      (node (ref "JP15") (pin "6") (pinfunction "6_6") (pintype "passive"))
      (node (ref "U13") (pin "45") (pinfunction "S16_45") (pintype "bidirectional"))
    )
    (net (code "57") (name "Net-(U13B-D)") (class "Default")
      (node (ref "C27") (pin "1") (pinfunction "1_1") (pintype "passive"))
      (node (ref "C31") (pin "2") (pinfunction "2_2") (pintype "passive"))
      (node (ref "TP8") (pin "TP") (pinfunction "TP_TP") (pintype "input"))
      (node (ref "U13") (pin "41") (pinfunction "D_41") (pintype "bidirectional"))
      (node (ref "U3") (pin "6") (pinfunction "IN-_6") (pintype "input"))
    )
    (net (code "58") (name "Net-(U13B-S1)") (class "Default")
      (node (ref "JP12") (pin "1") (pinfunction "1_1") (pintype "passive"))
      (node (ref "U13") (pin "25") (pinfunction "S1_25") (pintype "bidirectional"))
    )
    (net (code "59") (name "Net-(U13B-S2)") (class "Default")
      (node (ref "JP12") (pin "2") (pinfunction "2_2") (pintype "passive"))
      (node (ref "U13") (pin "26") (pinfunction "S2_26") (pintype "bidirectional"))
    )
    (net (code "60") (name "Net-(U13B-S3)") (class "Default")
      (node (ref "JP12") (pin "3") (pinfunction "3_3") (pintype "passive"))
      (node (ref "U13") (pin "27") (pinfunction "S3_27") (pintype "bidirectional"))
    )
    (net (code "61") (name "Net-(U13B-S4)") (class "Default")
      (node (ref "JP12") (pin "4") (pinfunction "4_4") (pintype "passive"))
      (node (ref "U13") (pin "28") (pinfunction "S4_28") (pintype "bidirectional"))
    )
    (net (code "62") (name "Net-(U13B-S5)") (class "Default")
      (node (ref "JP12") (pin "5") (pinfunction "5_5") (pintype "passive"))
      (node (ref "U13") (pin "29") (pinfunction "S5_29") (pintype "bidirectional"))
    )
    (net (code "63") (name "Net-(U13B-S6)") (class "Default")
      (node (ref "JP12") (pin "6") (pinfunction "6_6") (pintype "passive"))
      (node (ref "U13") (pin "30") (pinfunction "S6_30") (pintype "bidirectional"))
    )
    (net (code "64") (name "Net-(U13B-S7)") (class "Default")
      (node (ref "JP12") (pin "7") (pinfunction "7_7") (pintype "passive"))
      (node (ref "U13") (pin "31") (pinfunction "S7_31") (pintype "bidirectional"))
    )
    (net (code "65") (name "Net-(U13B-S8)") (class "Default")
      (node (ref "JP12") (pin "8") (pinfunction "8_8") (pintype "passive"))
      (node (ref "U13") (pin "32") (pinfunction "S8_32") (pintype "bidirectional"))
    )
    (net (code "66") (name "Net-(U13B-S9)") (class "Default")
      (node (ref "JP12") (pin "9") (pinfunction "9_9") (pintype "passive"))
      (node (ref "U13") (pin "33") (pinfunction "S9_33") (pintype "bidirectional"))
    )
    (net (code "67") (name "Net-(U13B-S10)") (class "Default")
      (node (ref "JP12") (pin "10") (pinfunction "10_10") (pintype "passive"))
      (node (ref "U13") (pin "34") (pinfunction "S10_34") (pintype "bidirectional"))
    )
    (net (code "68") (name "Net-(U13B-S11)") (class "Default")
      (node (ref "JP16") (pin "1") (pinfunction "1_1") (pintype "passive"))
      (node (ref "U13") (pin "35") (pinfunction "S11_35") (pintype "bidirectional"))
    )
    (net (code "69") (name "Net-(U13B-S12)") (class "Default")
      (node (ref "JP16") (pin "2") (pinfunction "2_2") (pintype "passive"))
      (node (ref "U13") (pin "36") (pinfunction "S12_36") (pintype "bidirectional"))
    )
    (net (code "70") (name "Net-(U13B-S13)") (class "Default")
      (node (ref "JP16") (pin "3") (pinfunction "3_3") (pintype "passive"))
      (node (ref "U13") (pin "37") (pinfunction "S13_37") (pintype "bidirectional"))
    )
    (net (code "71") (name "Net-(U13B-S14)") (class "Default")
      (node (ref "JP16") (pin "4") (pinfunction "4_4") (pintype "passive"))
      (node (ref "U13") (pin "38") (pinfunction "S14_38") (pintype "bidirectional"))
    )
    (net (code "72") (name "Net-(U13B-S15)") (class "Default")
      (node (ref "JP16") (pin "5") (pinfunction "5_5") (pintype "passive"))
      (node (ref "U13") (pin "39") (pinfunction "S15_39") (pintype "bidirectional"))
    )
    (net (code "73") (name "Net-(U13B-S16)") (class "Default")
      (node (ref "JP16") (pin "6") (pinfunction "6_6") (pintype "passive"))
      (node (ref "U13") (pin "40") (pinfunction "S16_40") (pintype "bidirectional"))
    )
    (net (code "74") (name "Net-(U14A-D)") (class "Default")
      (node (ref "C20") (pin "2") (pinfunction "2_2") (pintype "passive"))
      (node (ref "C29") (pin "1") (pinfunction "1_1") (pintype "passive"))
      (node (ref "TP5") (pin "TP") (pinfunction "TP_TP") (pintype "input"))
      (node (ref "U14") (pin "43") (pinfunction "D_43") (pintype "bidirectional"))
      (node (ref "U3") (pin "1") (pinfunction "OUT_1") (pintype "output"))
    )
    (net (code "75") (name "Net-(U14A-S1)") (class "Default")
      (node (ref "JP5") (pin "1") (pinfunction "1_1") (pintype "passive"))
      (node (ref "U14") (pin "12") (pinfunction "S1_12") (pintype "bidirectional"))
    )
    (net (code "76") (name "Net-(U14A-S2)") (class "Default")
      (node (ref "JP5") (pin "2") (pinfunction "2_2") (pintype "passive"))
      (node (ref "U14") (pin "11") (pinfunction "S2_11") (pintype "bidirectional"))
    )
    (net (code "77") (name "Net-(U14A-S3)") (class "Default")
      (node (ref "JP5") (pin "3") (pinfunction "3_3") (pintype "passive"))
      (node (ref "U14") (pin "10") (pinfunction "S3_10") (pintype "bidirectional"))
    )
    (net (code "78") (name "Net-(U14A-S4)") (class "Default")
      (node (ref "JP5") (pin "4") (pinfunction "4_4") (pintype "passive"))
      (node (ref "U14") (pin "9") (pinfunction "S4_9") (pintype "bidirectional"))
    )
    (net (code "79") (name "Net-(U14A-S5)") (class "Default")
      (node (ref "JP5") (pin "5") (pinfunction "5_5") (pintype "passive"))
      (node (ref "U14") (pin "8") (pinfunction "S5_8") (pintype "bidirectional"))
    )
    (net (code "80") (name "Net-(U14A-S6)") (class "Default")
      (node (ref "JP5") (pin "6") (pinfunction "6_6") (pintype "passive"))
      (node (ref "U14") (pin "7") (pinfunction "S6_7") (pintype "bidirectional"))
    )
    (net (code "81") (name "Net-(U14A-S7)") (class "Default")
      (node (ref "JP5") (pin "7") (pinfunction "7_7") (pintype "passive"))
      (node (ref "U14") (pin "6") (pinfunction "S7_6") (pintype "bidirectional"))
    )
    (net (code "82") (name "Net-(U14A-S8)") (class "Default")
      (node (ref "JP5") (pin "8") (pinfunction "8_8") (pintype "passive"))
      (node (ref "U14") (pin "5") (pinfunction "S8_5") (pintype "bidirectional"))
    )
    (net (code "83") (name "Net-(U14A-S9)") (class "Default")
      (node (ref "JP5") (pin "9") (pinfunction "9_9") (pintype "passive"))
      (node (ref "U14") (pin "4") (pinfunction "S9_4") (pintype "bidirectional"))
    )
    (net (code "84") (name "Net-(U14A-S10)") (class "Default")
      (node (ref "JP5") (pin "10") (pinfunction "10_10") (pintype "passive"))
      (node (ref "U14") (pin "3") (pinfunction "S10_3") (pintype "bidirectional"))
    )
    (net (code "85") (name "Net-(U14A-S11)") (class "Default")
      (node (ref "JP13") (pin "1") (pinfunction "1_1") (pintype "passive"))
      (node (ref "U14") (pin "2") (pinfunction "S11_2") (pintype "bidirectional"))
    )
    (net (code "86") (name "Net-(U14A-S12)") (class "Default")
      (node (ref "JP13") (pin "2") (pinfunction "2_2") (pintype "passive"))
      (node (ref "U14") (pin "1") (pinfunction "S12_1") (pintype "bidirectional"))
    )
    (net (code "87") (name "Net-(U14A-S13)") (class "Default")
      (node (ref "JP13") (pin "3") (pinfunction "3_3") (pintype "passive"))
      (node (ref "U14") (pin "48") (pinfunction "S13_48") (pintype "bidirectional"))
    )
    (net (code "88") (name "Net-(U14A-S14)") (class "Default")
      (node (ref "JP13") (pin "4") (pinfunction "4_4") (pintype "passive"))
      (node (ref "U14") (pin "47") (pinfunction "S14_47") (pintype "bidirectional"))
    )
    (net (code "89") (name "Net-(U14A-S15)") (class "Default")
      (node (ref "JP13") (pin "5") (pinfunction "5_5") (pintype "passive"))
      (node (ref "U14") (pin "46") (pinfunction "S15_46") (pintype "bidirectional"))
    )
    (net (code "90") (name "Net-(U14A-S16)") (class "Default")
      (node (ref "JP13") (pin "6") (pinfunction "6_6") (pintype "passive"))
      (node (ref "U14") (pin "45") (pinfunction "S16_45") (pintype "bidirectional"))
    )
    (net (code "91") (name "Net-(U14B-D)") (class "Default")
      (node (ref "C30") (pin "2") (pinfunction "2_2") (pintype "passive"))
      (node (ref "C32") (pin "2") (pinfunction "2_2") (pintype "passive"))
      (node (ref "TP6") (pin "TP") (pinfunction "TP_TP") (pintype "input"))
      (node (ref "U14") (pin "41") (pinfunction "D_41") (pintype "bidirectional"))
      (node (ref "U2") (pin "8") (pinfunction "D_8") (pintype "bidirectional"))
    )
    (net (code "92") (name "Net-(U14B-S1)") (class "Default")
      (node (ref "JP6") (pin "1") (pinfunction "1_1") (pintype "passive"))
      (node (ref "U14") (pin "25") (pinfunction "S1_25") (pintype "bidirectional"))
    )
    (net (code "93") (name "Net-(U14B-S2)") (class "Default")
      (node (ref "JP6") (pin "2") (pinfunction "2_2") (pintype "passive"))
      (node (ref "U14") (pin "26") (pinfunction "S2_26") (pintype "bidirectional"))
    )
    (net (code "94") (name "Net-(U14B-S3)") (class "Default")
      (node (ref "JP6") (pin "3") (pinfunction "3_3") (pintype "passive"))
      (node (ref "U14") (pin "27") (pinfunction "S3_27") (pintype "bidirectional"))
    )
    (net (code "95") (name "Net-(U14B-S4)") (class "Default")
      (node (ref "JP6") (pin "4") (pinfunction "4_4") (pintype "passive"))
      (node (ref "U14") (pin "28") (pinfunction "S4_28") (pintype "bidirectional"))
    )
    (net (code "96") (name "Net-(U14B-S5)") (class "Default")
      (node (ref "JP6") (pin "5") (pinfunction "5_5") (pintype "passive"))
      (node (ref "U14") (pin "29") (pinfunction "S5_29") (pintype "bidirectional"))
    )
    (net (code "97") (name "Net-(U14B-S6)") (class "Default")
      (node (ref "JP6") (pin "6") (pinfunction "6_6") (pintype "passive"))
      (node (ref "U14") (pin "30") (pinfunction "S6_30") (pintype "bidirectional"))
    )
    (net (code "98") (name "Net-(U14B-S7)") (class "Default")
      (node (ref "JP6") (pin "7") (pinfunction "7_7") (pintype "passive"))
      (node (ref "U14") (pin "31") (pinfunction "S7_31") (pintype "bidirectional"))
    )
    (net (code "99") (name "Net-(U14B-S8)") (class "Default")
      (node (ref "JP6") (pin "8") (pinfunction "8_8") (pintype "passive"))
      (node (ref "U14") (pin "32") (pinfunction "S8_32") (pintype "bidirectional"))
    )
    (net (code "100") (name "Net-(U14B-S9)") (class "Default")
      (node (ref "JP6") (pin "9") (pinfunction "9_9") (pintype "passive"))
      (node (ref "U14") (pin "33") (pinfunction "S9_33") (pintype "bidirectional"))
    )
    (net (code "101") (name "Net-(U14B-S10)") (class "Default")
      (node (ref "JP6") (pin "10") (pinfunction "10_10") (pintype "passive"))
      (node (ref "U14") (pin "34") (pinfunction "S10_34") (pintype "bidirectional"))
    )
    (net (code "102") (name "Net-(U14B-S11)") (class "Default")
      (node (ref "JP14") (pin "1") (pinfunction "1_1") (pintype "passive"))
      (node (ref "U14") (pin "35") (pinfunction "S11_35") (pintype "bidirectional"))
    )
    (net (code "103") (name "Net-(U14B-S12)") (class "Default")
      (node (ref "JP14") (pin "2") (pinfunction "2_2") (pintype "passive"))
      (node (ref "U14") (pin "36") (pinfunction "S12_36") (pintype "bidirectional"))
    )
    (net (code "104") (name "Net-(U14B-S13)") (class "Default")
      (node (ref "JP14") (pin "3") (pinfunction "3_3") (pintype "passive"))
      (node (ref "U14") (pin "37") (pinfunction "S13_37") (pintype "bidirectional"))
    )
    (net (code "105") (name "Net-(U14B-S14)") (class "Default")
      (node (ref "JP14") (pin "4") (pinfunction "4_4") (pintype "passive"))
      (node (ref "U14") (pin "38") (pinfunction "S14_38") (pintype "bidirectional"))
    )
    (net (code "106") (name "Net-(U14B-S15)") (class "Default")
      (node (ref "JP14") (pin "5") (pinfunction "5_5") (pintype "passive"))
      (node (ref "U14") (pin "39") (pinfunction "S15_39") (pintype "bidirectional"))
    )
    (net (code "107") (name "Net-(U14B-S16)") (class "Default")
      (node (ref "JP14") (pin "6") (pinfunction "6_6") (pintype "passive"))
      (node (ref "U14") (pin "40") (pinfunction "S16_40") (pintype "bidirectional"))
    )
    (net (code "108") (name "Net-(U15-D)") (class "Default")
      (node (ref "C25") (pin "1") (pinfunction "1_1") (pintype "passive"))
      (node (ref "U15") (pin "5") (pinfunction "D_5") (pintype "bidirectional"))
    )
    (net (code "109") (name "Net-(U15-S1)") (class "Default")
      (node (ref "R20") (pin "1") (pinfunction "1_1") (pintype "passive"))
      (node (ref "U15") (pin "4") (pinfunction "S1_4") (pintype "bidirectional"))
    )
    (net (code "110") (name "Net-(U15-S2)") (class "Default")
      (node (ref "RA") (pin "2") (pinfunction "2_2") (pintype "passive"))
      (node (ref "TP10") (pin "TP") (pinfunction "TP_TP") (pintype "input"))
      (node (ref "U15") (pin "6") (pinfunction "S2_6") (pintype "bidirectional"))
    )
    (net (code "111") (name "PA0") (class "Default")
      (node (ref "JP1") (pin "12") (pinfunction "12_12") (pintype "passive"))
      (node (ref "S1") (pin "1") (pinfunction "0_1") (pintype "passive"))
      (node (ref "S1") (pin "2") (pinfunction "0_2") (pintype "passive"))
    )
    (net (code "112") (name "PA2") (class "Default")
      (node (ref "JP1") (pin "14") (pinfunction "14_14") (pintype "passive"))
      (node (ref "R5") (pin "1") (pinfunction "1_1") (pintype "passive"))
      (node (ref "U6") (pin "30") (pinfunction "MDIO_30") (pintype "bidirectional"))
    )
    (net (code "113") (name "PA7") (class "Default")
      (node (ref "JP1") (pin "17") (pinfunction "17_17") (pintype "passive"))
      (node (ref "RS2") (pin "1") (pinfunction "1_1") (pintype "passive"))
      (node (ref "U6") (pin "40") (pinfunction "CRS_DV_40") (pintype "output"))
    )
    (net (code "114") (name "PA9") (class "Default")
      (node (ref "JP10") (pin "1") (pinfunction "1_1") (pintype "passive"))
      (node (ref "JP2") (pin "44") (pinfunction "44_44") (pintype "passive"))
      (node (ref "R22") (pin "2") (pinfunction "2_2") (pintype "passive"))
    )
    (net (code "115") (name "PB4") (class "Default")
      (node (ref "JP2") (pin "25") (pinfunction "25_25") (pintype "passive"))
      (node (ref "U5") (pin "16") (pinfunction "A1_16") (pintype "input"))
    )
    (net (code "116") (name "PB5") (class "Default")
      (node (ref "JP2") (pin "26") (pinfunction "26_26") (pintype "passive"))
      (node (ref "U5") (pin "15") (pinfunction "A2_15") (pintype "input"))
    )
    (net (code "117") (name "PB6") (class "Default")
      (node (ref "JP2") (pin "23") (pinfunction "23_23") (pintype "passive"))
      (node (ref "JP7") (pin "3") (pinfunction "3_3") (pintype "passive"))
      (node (ref "R12") (pin "1") (pinfunction "1_1") (pintype "passive"))
      (node (ref "U1") (pin "16") (pinfunction "SCL_16") (pintype "bidirectional"))
      (node (ref "U4") (pin "6") (pinfunction "SCL_6") (pintype "input"))
    )
    (net (code "118") (name "PB7") (class "Default")
      (node (ref "JP2") (pin "24") (pinfunction "24_24") (pintype "passive"))
      (node (ref "U5") (pin "17") (pinfunction "A0_17") (pintype "input"))
    )
    (net (code "119") (name "PB8") (class "Default")
      (node (ref "JP2") (pin "19") (pinfunction "19_19") (pintype "passive"))
      (node (ref "U1") (pin "8") (pinfunction "MCLK_8") (pintype "bidirectional"))
    )
    (net (code "120") (name "PB9") (class "Default")
      (node (ref "JP2") (pin "20") (pinfunction "20_20") (pintype "passive"))
      (node (ref "JP7") (pin "2") (pinfunction "2_2") (pintype "passive"))
      (node (ref "R21") (pin "1") (pinfunction "1_1") (pintype "passive"))
      (node (ref "U1") (pin "15") (pinfunction "SDA_15") (pintype "bidirectional"))
      (node (ref "U4") (pin "5") (pinfunction "SDA_5") (pintype "open_collector"))
    )
    (net (code "121") (name "PB11") (class "Default")
      (node (ref "JP1") (pin "35") (pinfunction "35_35") (pintype "passive"))
      (node (ref "U6") (pin "2") (pinfunction "TX_EN_2") (pintype "input"))
    )
    (net (code "122") (name "PB12") (class "Default")
      (node (ref "JP1") (pin "36") (pinfunction "36_36") (pintype "passive"))
      (node (ref "U6") (pin "3") (pinfunction "TXD_0_3") (pintype "input"))
    )
    (net (code "123") (name "PB13") (class "Default")
      (node (ref "JP1") (pin "37") (pinfunction "37_37") (pintype "passive"))
      (node (ref "U6") (pin "4") (pinfunction "TXD_1_4") (pintype "input"))
    )
    (net (code "124") (name "PC1") (class "Default")
      (node (ref "JP1") (pin "7") (pinfunction "7_7") (pintype "passive"))
      (node (ref "U6") (pin "31") (pinfunction "MDC_31") (pintype "input"))
    )
    (net (code "125") (name "PC2") (class "Default")
      (node (ref "C31") (pin "1") (pinfunction "1_1") (pintype "passive"))
      (node (ref "JP1") (pin "10") (pinfunction "10_10") (pintype "passive"))
      (node (ref "R18") (pin "2") (pinfunction "2_2") (pintype "passive"))
      (node (ref "RFB1") (pin "2") (pinfunction "2_2") (pintype "passive"))
      (node (ref "RFB2") (pin "2") (pinfunction "2_2") (pintype "passive"))
      (node (ref "RFB3") (pin "2") (pinfunction "2_2") (pintype "passive"))
      (node (ref "RFB4") (pin "2") (pinfunction "2_2") (pintype "passive"))
      (node (ref "RFB5") (pin "2") (pinfunction "2_2") (pintype "passive"))
      (node (ref "RFB6") (pin "2") (pinfunction "2_2") (pintype "passive"))
      (node (ref "RFB7") (pin "2") (pinfunction "2_2") (pintype "passive"))
      (node (ref "RFB8") (pin "2") (pinfunction "2_2") (pintype "passive"))
      (node (ref "TP4") (pin "TP") (pinfunction "TP_TP") (pintype "input"))
      (node (ref "U3") (pin "7") (pinfunction "OUT_7") (pintype "output"))
    )
    (net (code "126") (name "PC4") (class "Default")
      (node (ref "JP1") (pin "20") (pinfunction "20_20") (pintype "passive"))
      (node (ref "U6") (pin "43") (pinfunction "RXD_0_43") (pintype "output"))
    )
    (net (code "127") (name "PC5") (class "Default")
      (node (ref "JP1") (pin "19") (pinfunction "19_19") (pintype "passive"))
      (node (ref "U6") (pin "44") (pinfunction "RXD_1_44") (pintype "output"))
    )
    (net (code "128") (name "PC9") (class "Default")
      (node (ref "JP2") (pin "46") (pinfunction "46_46") (pintype "passive"))
      (node (ref "SJ2") (pin "2") (pinfunction "2_2") (pintype "passive"))
    )
    (net (code "129") (name "PC10") (class "Default")
      (node (ref "JP2") (pin "37") (pinfunction "37_37") (pintype "passive"))
      (node (ref "U11") (pin "6") (pinfunction "SCK_6") (pintype "input"))
      (node (ref "U13") (pin "19") (pinfunction "SCLK_19") (pintype "input"))
      (node (ref "U14") (pin "19") (pinfunction "SCLK_19") (pintype "input"))
      (node (ref "U8") (pin "6") (pinfunction "SCK_6") (pintype "input"))
      (node (ref "U9") (pin "6") (pinfunction "SCK_6") (pintype "input"))
    )
    (net (code "130") (name "PC11") (class "Default")
      (node (ref "JP2") (pin "38") (pinfunction "38_38") (pintype "passive"))
      (node (ref "U11") (pin "2") (pinfunction "SO_2") (pintype "tri_state"))
      (node (ref "U8") (pin "2") (pinfunction "SO_2") (pintype "tri_state"))
      (node (ref "U9") (pin "2") (pinfunction "SO_2") (pintype "tri_state"))
    )
    (net (code "131") (name "PC12") (class "Default")
      (node (ref "JP2") (pin "35") (pinfunction "35_35") (pintype "passive"))
      (node (ref "U11") (pin "5") (pinfunction "SI_5") (pintype "input"))
      (node (ref "U13") (pin "18") (pinfunction "DIN_18") (pintype "input"))
      (node (ref "U14") (pin "18") (pinfunction "DIN_18") (pintype "input"))
      (node (ref "U8") (pin "5") (pinfunction "SI_5") (pintype "input"))
      (node (ref "U9") (pin "5") (pinfunction "SI_5") (pintype "input"))
    )
    (net (code "132") (name "PD0") (class "Default")
      (node (ref "JP2") (pin "36") (pinfunction "36_36") (pintype "passive"))
      (node (ref "U8") (pin "1") (pinfunction "~{CS}_1") (pintype "input"))
      (node (ref "U9") (pin "1") (pinfunction "~{CS}_1") (pintype "input"))
    )
    (net (code "133") (name "PD1") (class "Default")
      (node (ref "JP2") (pin "33") (pinfunction "33_33") (pintype "passive"))
      (node (ref "U11") (pin "1") (pinfunction "~{CS}_1") (pintype "input"))
    )
    (net (code "134") (name "PD2") (class "Default")
      (node (ref "JP2") (pin "34") (pinfunction "34_34") (pintype "passive"))
      (node (ref "U13") (pin "17") (pinfunction "~{SYNC}_17") (pintype "input"))
      (node (ref "U14") (pin "17") (pinfunction "~{SYNC}_17") (pintype "input"))
    )
    (net (code "135") (name "PD8") (class "Default")
      (node (ref "JP1") (pin "40") (pinfunction "40_40") (pintype "passive"))
      (node (ref "U7") (pin "3") (pinfunction "EN_3") (pintype "input"))
    )
    (net (code "136") (name "PD9") (class "Default")
      (node (ref "JP1") (pin "41") (pinfunction "41_41") (pintype "passive"))
      (node (ref "U7") (pin "4") (pinfunction "~{FAULT}_4") (pintype "output"))
    )
    (net (code "137") (name "PE2") (class "Default")
      (node (ref "J3") (pin "3") (pinfunction "2_3") (pintype "passive"))
      (node (ref "JP2") (pin "15") (pinfunction "15_15") (pintype "passive"))
    )
    (net (code "138") (name "PE4") (class "Default")
      (node (ref "JP2") (pin "13") (pinfunction "13_13") (pintype "passive"))
      (node (ref "U15") (pin "1") (pinfunction "IN_1") (pintype "input"))
    )
    (net (code "139") (name "PE5") (class "Default")
      (node (ref "JP2") (pin "14") (pinfunction "14_14") (pintype "passive"))
      (node (ref "U2") (pin "1") (pinfunction "A0_1") (pintype "input"))
    )
    (net (code "140") (name "PE6") (class "Default")
      (node (ref "JP2") (pin "11") (pinfunction "11_11") (pintype "passive"))
      (node (ref "U2") (pin "10") (pinfunction "A1_10") (pintype "input"))
    )
    (net (code "141") (name "RD_N") (class "Default")
      (node (ref "J2") (pin "6") (pinfunction "RD-_6") (pintype "passive"))
      (node (ref "R4") (pin "1") (pinfunction "1_1") (pintype "passive"))
      (node (ref "U6") (pin "13") (pinfunction "RD-_13") (pintype "bidirectional"))
    )
    (net (code "142") (name "RD_P") (class "Default")
      (node (ref "J2") (pin "4") (pinfunction "RD+_4") (pintype "passive"))
      (node (ref "R3") (pin "1") (pinfunction "1_1") (pintype "passive"))
      (node (ref "U6") (pin "14") (pinfunction "RD+_14") (pintype "bidirectional"))
    )
    (net (code "143") (name "RFB") (class "Default")
      (node (ref "R19") (pin "1") (pinfunction "1_1") (pintype "passive"))
      (node (ref "U1") (pin "4") (pinfunction "RFB_4") (pintype "bidirectional"))
    )
    (net (code "144") (name "TD_N") (class "Default")
      (node (ref "J2") (pin "3") (pinfunction "TD-_3") (pintype "passive"))
      (node (ref "R2") (pin "1") (pinfunction "1_1") (pintype "passive"))
      (node (ref "U6") (pin "16") (pinfunction "TD-_16") (pintype "bidirectional"))
    )
    (net (code "145") (name "TD_P") (class "Default")
      (node (ref "J2") (pin "1") (pinfunction "TD+_1") (pintype "passive"))
      (node (ref "R1") (pin "1") (pinfunction "1_1") (pintype "passive"))
      (node (ref "U6") (pin "17") (pinfunction "TD+_17") (pintype "bidirectional"))
    )
    (net (code "146") (name "USB_N") (class "Default")
      (node (ref "J1") (pin "2") (pinfunction "D-_2") (pintype "passive"))
      (node (ref "JP1") (pin "38") (pinfunction "38_38") (pintype "passive"))
    )
    (net (code "147") (name "USB_P") (class "Default")
      (node (ref "J1") (pin "3") (pinfunction "D+_3") (pintype "passive"))
      (node (ref "JP1") (pin "39") (pinfunction "39_39") (pintype "passive"))
    )
    (net (code "148") (name "VCC") (class "Default")
      (node (ref "C10") (pin "1") (pinfunction "1_1") (pintype "passive"))
      (node (ref "C11") (pin "1") (pinfunction "1_1") (pintype "passive"))
      (node (ref "C12") (pin "1") (pinfunction "1_1") (pintype "passive"))
      (node (ref "C13") (pin "2") (pinfunction "2_2") (pintype "passive"))
      (node (ref "C14") (pin "1") (pinfunction "1_1") (pintype "passive"))
      (node (ref "C22") (pin "1") (pinfunction "1_1") (pintype "passive"))
      (node (ref "C3") (pin "1") (pinfunction "1_1") (pintype "passive"))
      (node (ref "C4") (pin "1") (pinfunction "1_1") (pintype "passive"))
      (node (ref "C5") (pin "1") (pinfunction "1_1") (pintype "passive"))
      (node (ref "C6") (pin "1") (pinfunction "1_1") (pintype "passive"))
      (node (ref "C7") (pin "1") (pinfunction "1_1") (pintype "passive"))
      (node (ref "C8") (pin "1") (pinfunction "1_1") (pintype "passive"))
      (node (ref "C9") (pin "1") (pinfunction "1_1") (pintype "passive"))
      (node (ref "J2") (pin "2") (pinfunction "TCT_2") (pintype "passive"))
      (node (ref "J2") (pin "5") (pinfunction "RCT_5") (pintype "passive"))
      (node (ref "J2") (pin "AG") (pinfunction "AG_AG") (pintype "passive"))
      (node (ref "J2") (pin "AY") (pinfunction "AY_AY") (pintype "passive"))
      (node (ref "JP4") (pin "1") (pinfunction "1_1") (pintype "passive"))
      (node (ref "R1") (pin "2") (pinfunction "2_2") (pintype "passive"))
      (node (ref "R11") (pin "2") (pinfunction "2_2") (pintype "passive"))
      (node (ref "R12") (pin "2") (pinfunction "2_2") (pintype "passive"))
      (node (ref "R16") (pin "2") (pinfunction "2_2") (pintype "passive"))
      (node (ref "R2") (pin "2") (pinfunction "2_2") (pintype "passive"))
      (node (ref "R21") (pin "2") (pinfunction "2_2") (pintype "passive"))
      (node (ref "R3") (pin "2") (pinfunction "2_2") (pintype "passive"))
      (node (ref "R4") (pin "2") (pinfunction "2_2") (pintype "passive"))
      (node (ref "R5") (pin "2") (pinfunction "2_2") (pintype "passive"))
      (node (ref "R7") (pin "2") (pinfunction "2_2") (pintype "passive"))
      (node (ref "R8") (pin "2") (pinfunction "2_2") (pintype "passive"))
      (node (ref "RS1") (pin "1") (pinfunction "1_1") (pintype "passive"))
      (node (ref "RS3") (pin "1") (pinfunction "1_1") (pintype "passive"))
      (node (ref "RS4") (pin "1") (pinfunction "1_1") (pintype "passive"))
      (node (ref "TP1") (pin "TP") (pinfunction "TP_TP") (pintype "input"))
      (node (ref "U1") (pin "10") (pinfunction "AVDD1_10") (pintype "bidirectional"))
      (node (ref "U1") (pin "11") (pinfunction "AVDD2_11") (pintype "bidirectional"))
      (node (ref "U1") (pin "9") (pinfunction "DVDD_9") (pintype "bidirectional"))
      (node (ref "U11") (pin "7") (pinfunction "VBAT_7") (pintype "power_in"))
      (node (ref "U11") (pin "8") (pinfunction "VDD_8") (pintype "power_in"))
      (node (ref "U13") (pin "13") (pinfunction "VDD_13") (pintype "power_in"))
      (node (ref "U13") (pin "14") (pinfunction "VDD1_14") (pintype "power_in"))
      (node (ref "U14") (pin "13") (pinfunction "VDD_13") (pintype "power_in"))
      (node (ref "U14") (pin "14") (pinfunction "VDD1_14") (pintype "power_in"))
      (node (ref "U15") (pin "2") (pinfunction "VDD_2") (pintype "power_in"))
      (node (ref "U2") (pin "5") (pinfunction "EN_5") (pintype "input"))
      (node (ref "U2") (pin "6") (pinfunction "VDD_6") (pintype "power_in"))
      (node (ref "U3") (pin "8") (pinfunction "V+_8") (pintype "power_in"))
      (node (ref "U4") (pin "8") (pinfunction "VCC_8") (pintype "power_in"))
      (node (ref "U5") (pin "1") (pinfunction "VDD_1") (pintype "power_in"))
      (node (ref "U5") (pin "18") (pinfunction "EN_18") (pintype "input"))
      (node (ref "U6") (pin "22") (pinfunction "AVDD33_22") (pintype "power_in"))
      (node (ref "U6") (pin "32") (pinfunction "IOVDD33__32") (pintype "power_in"))
      (node (ref "U6") (pin "48") (pinfunction "IOVDD33_48") (pintype "power_in"))
      (node (ref "U8") (pin "3") (pinfunction "~{WP}_3") (pintype "input"))
      (node (ref "U8") (pin "7") (pinfunction "~{HOLD}_7") (pintype "input"))
      (node (ref "U8") (pin "8") (pinfunction "VDD_8") (pintype "power_in"))
      (node (ref "U9") (pin "3") (pinfunction "~{WP}_3") (pintype "input"))
      (node (ref "U9") (pin "7") (pinfunction "~{HOLD}_7") (pintype "input"))
      (node (ref "U9") (pin "8") (pinfunction "VDD_8") (pintype "power_in"))
    )
    (net (code "149") (name "VCC{slash}2") (class "Default")
      (node (ref "C26") (pin "2") (pinfunction "2_2") (pintype "passive"))
      (node (ref "R16") (pin "1") (pinfunction "1_1") (pintype "passive"))
      (node (ref "R17") (pin "2") (pinfunction "2_2") (pintype "passive"))
      (node (ref "R20") (pin "2") (pinfunction "2_2") (pintype "passive"))
      (node (ref "TP9") (pin "TP") (pinfunction "TP_TP") (pintype "input"))
      (node (ref "U3") (pin "3") (pinfunction "IN+_3") (pintype "input"))
      (node (ref "U3") (pin "5") (pinfunction "IN+_5") (pintype "input"))
    )
    (net (code "150") (name "VDD") (class "Default")
      (node (ref "JP2") (pin "22") (pinfunction "22_22") (pintype "passive"))
      (node (ref "JP3") (pin "2") (pinfunction "2_2") (pintype "passive"))
      (node (ref "JP7") (pin "4") (pinfunction "4_4") (pintype "passive"))
      (node (ref "S1") (pin "3") (pinfunction "1_3") (pintype "passive"))
      (node (ref "S1") (pin "4") (pinfunction "1_4") (pintype "passive"))
    )
    (net (code "151") (name "VIN") (class "Default")
      (node (ref "R18") (pin "1") (pinfunction "1_1") (pintype "passive"))
      (node (ref "R19") (pin "2") (pinfunction "2_2") (pintype "passive"))
      (node (ref "U1") (pin "5") (pinfunction "VIN_5") (pintype "bidirectional"))
    )
    (net (code "152") (name "VOUT") (class "Default")
      (node (ref "C25") (pin "2") (pinfunction "2_2") (pintype "passive"))
      (node (ref "TP3") (pin "TP") (pinfunction "TP_TP") (pintype "input"))
      (node (ref "U1") (pin "6") (pinfunction "VOUT_6") (pintype "bidirectional"))
    )
    (net (code "153") (name "unconnected-(JP1-Pad3)") (class "Default")
      (node (ref "JP1") (pin "3") (pinfunction "3_3") (pintype "passive"))
    )
    (net (code "154") (name "unconnected-(JP1-Pad4)") (class "Default")
      (node (ref "JP1") (pin "4") (pinfunction "4_4") (pintype "passive"))
    )
    (net (code "155") (name "unconnected-(JP1-Pad5)") (class "Default")
      (node (ref "JP1") (pin "5") (pinfunction "5_5") (pintype "passive"))
    )
    (net (code "156") (name "unconnected-(JP1-Pad8)") (class "Default")
      (node (ref "JP1") (pin "8") (pinfunction "8_8") (pintype "passive"))
    )
    (net (code "157") (name "unconnected-(JP1-Pad9)") (class "Default")
      (node (ref "JP1") (pin "9") (pinfunction "9_9") (pintype "passive"))
    )
    (net (code "158") (name "unconnected-(JP1-Pad13)") (class "Default")
      (node (ref "JP1") (pin "13") (pinfunction "13_13") (pintype "passive"))
    )
    (net (code "159") (name "unconnected-(JP1-Pad15)") (class "Default")
      (node (ref "JP1") (pin "15") (pinfunction "15_15") (pintype "passive"))
    )
    (net (code "160") (name "unconnected-(JP1-Pad16)") (class "Default")
      (node (ref "JP1") (pin "16") (pinfunction "16_16") (pintype "passive"))
    )
    (net (code "161") (name "unconnected-(JP1-Pad18)") (class "Default")
      (node (ref "JP1") (pin "18") (pinfunction "18_18") (pintype "passive"))
    )
    (net (code "162") (name "unconnected-(JP1-Pad21)") (class "Default")
      (node (ref "JP1") (pin "21") (pinfunction "21_21") (pintype "passive"))
    )
    (net (code "163") (name "unconnected-(JP1-Pad22)") (class "Default")
      (node (ref "JP1") (pin "22") (pinfunction "22_22") (pintype "passive"))
    )
    (net (code "164") (name "unconnected-(JP1-Pad23)") (class "Default")
      (node (ref "JP1") (pin "23") (pinfunction "23_23") (pintype "passive"))
    )
    (net (code "165") (name "unconnected-(JP1-Pad24)") (class "Default")
      (node (ref "JP1") (pin "24") (pinfunction "24_24") (pintype "passive"))
    )
    (net (code "166") (name "unconnected-(JP1-Pad25)") (class "Default")
      (node (ref "JP1") (pin "25") (pinfunction "25_25") (pintype "passive"))
    )
    (net (code "167") (name "unconnected-(JP1-Pad26)") (class "Default")
      (node (ref "JP1") (pin "26") (pinfunction "26_26") (pintype "passive"))
    )
    (net (code "168") (name "unconnected-(JP1-Pad27)") (class "Default")
      (node (ref "JP1") (pin "27") (pinfunction "27_27") (pintype "passive"))
    )
    (net (code "169") (name "unconnected-(JP1-Pad28)") (class "Default")
      (node (ref "JP1") (pin "28") (pinfunction "28_28") (pintype "passive"))
    )
    (net (code "170") (name "unconnected-(JP1-Pad29)") (class "Default")
      (node (ref "JP1") (pin "29") (pinfunction "29_29") (pintype "passive"))
    )
    (net (code "171") (name "unconnected-(JP1-Pad30)") (class "Default")
      (node (ref "JP1") (pin "30") (pinfunction "30_30") (pintype "passive"))
    )
    (net (code "172") (name "unconnected-(JP1-Pad31)") (class "Default")
      (node (ref "JP1") (pin "31") (pinfunction "31_31") (pintype "passive"))
    )
    (net (code "173") (name "unconnected-(JP1-Pad32)") (class "Default")
      (node (ref "JP1") (pin "32") (pinfunction "32_32") (pintype "passive"))
    )
    (net (code "174") (name "unconnected-(JP1-Pad33)") (class "Default")
      (node (ref "JP1") (pin "33") (pinfunction "33_33") (pintype "passive"))
    )
    (net (code "175") (name "unconnected-(JP1-Pad34)") (class "Default")
      (node (ref "JP1") (pin "34") (pinfunction "34_34") (pintype "passive"))
    )
    (net (code "176") (name "unconnected-(JP1-Pad42)") (class "Default")
      (node (ref "JP1") (pin "42") (pinfunction "42_42") (pintype "passive"))
    )
    (net (code "177") (name "unconnected-(JP1-Pad43)") (class "Default")
      (node (ref "JP1") (pin "43") (pinfunction "43_43") (pintype "passive"))
    )
    (net (code "178") (name "unconnected-(JP1-Pad44)") (class "Default")
      (node (ref "JP1") (pin "44") (pinfunction "44_44") (pintype "passive"))
    )
    (net (code "179") (name "unconnected-(JP1-Pad45)") (class "Default")
      (node (ref "JP1") (pin "45") (pinfunction "45_45") (pintype "passive"))
    )
    (net (code "180") (name "unconnected-(JP1-Pad46)") (class "Default")
      (node (ref "JP1") (pin "46") (pinfunction "46_46") (pintype "passive"))
    )
    (net (code "181") (name "unconnected-(JP1-Pad47)") (class "Default")
      (node (ref "JP1") (pin "47") (pinfunction "47_47") (pintype "passive"))
    )
    (net (code "182") (name "unconnected-(JP1-Pad48)") (class "Default")
      (node (ref "JP1") (pin "48") (pinfunction "48_48") (pintype "passive"))
    )
    (net (code "183") (name "unconnected-(JP2-Pad7)") (class "Default")
      (node (ref "JP2") (pin "7") (pinfunction "7_7") (pintype "passive"))
    )
    (net (code "184") (name "unconnected-(JP2-Pad8)") (class "Default")
      (node (ref "JP2") (pin "8") (pinfunction "8_8") (pintype "passive"))
    )
    (net (code "185") (name "unconnected-(JP2-Pad9)") (class "Default")
      (node (ref "JP2") (pin "9") (pinfunction "9_9") (pintype "passive"))
    )
    (net (code "186") (name "unconnected-(JP2-Pad10)") (class "Default")
      (node (ref "JP2") (pin "10") (pinfunction "10_10") (pintype "passive"))
    )
    (net (code "187") (name "unconnected-(JP2-Pad12)") (class "Default")
      (node (ref "JP2") (pin "12") (pinfunction "12_12") (pintype "passive"))
    )
    (net (code "188") (name "unconnected-(JP2-Pad16)") (class "Default")
      (node (ref "JP2") (pin "16") (pinfunction "16_16") (pintype "passive"))
    )
    (net (code "189") (name "unconnected-(JP2-Pad17)") (class "Default")
      (node (ref "JP2") (pin "17") (pinfunction "17_17") (pintype "passive"))
    )
    (net (code "190") (name "unconnected-(JP2-Pad18)") (class "Default")
      (node (ref "JP2") (pin "18") (pinfunction "18_18") (pintype "passive"))
    )
    (net (code "191") (name "unconnected-(JP2-Pad21)") (class "Default")
      (node (ref "JP2") (pin "21") (pinfunction "21_21") (pintype "passive"))
    )
    (net (code "192") (name "unconnected-(JP2-Pad27)") (class "Default")
      (node (ref "JP2") (pin "27") (pinfunction "27_27") (pintype "passive"))
    )
    (net (code "193") (name "unconnected-(JP2-Pad28)") (class "Default")
      (node (ref "JP2") (pin "28") (pinfunction "28_28") (pintype "passive"))
    )
    (net (code "194") (name "unconnected-(JP2-Pad29)") (class "Default")
      (node (ref "JP2") (pin "29") (pinfunction "29_29") (pintype "passive"))
    )
    (net (code "195") (name "unconnected-(JP2-Pad30)") (class "Default")
      (node (ref "JP2") (pin "30") (pinfunction "30_30") (pintype "passive"))
    )
    (net (code "196") (name "unconnected-(JP2-Pad31)") (class "Default")
      (node (ref "JP2") (pin "31") (pinfunction "31_31") (pintype "passive"))
    )
    (net (code "197") (name "unconnected-(JP2-Pad32)") (class "Default")
      (node (ref "JP2") (pin "32") (pinfunction "32_32") (pintype "passive"))
    )
    (net (code "198") (name "unconnected-(JP2-Pad39)") (class "Default")
      (node (ref "JP2") (pin "39") (pinfunction "39_39") (pintype "passive"))
    )
    (net (code "199") (name "unconnected-(JP2-Pad40)") (class "Default")
      (node (ref "JP2") (pin "40") (pinfunction "40_40") (pintype "passive"))
    )
    (net (code "200") (name "unconnected-(JP2-Pad41)") (class "Default")
      (node (ref "JP2") (pin "41") (pinfunction "41_41") (pintype "passive"))
    )
    (net (code "201") (name "unconnected-(JP2-Pad42)") (class "Default")
      (node (ref "JP2") (pin "42") (pinfunction "42_42") (pintype "passive"))
    )
    (net (code "202") (name "unconnected-(JP2-Pad43)") (class "Default")
      (node (ref "JP2") (pin "43") (pinfunction "43_43") (pintype "passive"))
    )
    (net (code "203") (name "unconnected-(JP2-Pad45)") (class "Default")
      (node (ref "JP2") (pin "45") (pinfunction "45_45") (pintype "passive"))
    )
    (net (code "204") (name "unconnected-(JP2-Pad47)") (class "Default")
      (node (ref "JP2") (pin "47") (pinfunction "47_47") (pintype "passive"))
    )
    (net (code "205") (name "unconnected-(JP2-Pad48)") (class "Default")
      (node (ref "JP2") (pin "48") (pinfunction "48_48") (pintype "passive"))
    )
    (net (code "206") (name "unconnected-(U5-S9-Pad11)") (class "Default")
      (node (ref "U5") (pin "11") (pinfunction "S9_11") (pintype "bidirectional"))
    )
    (net (code "207") (name "unconnected-(U5-S10-Pad10)") (class "Default")
      (node (ref "U5") (pin "10") (pinfunction "S10_10") (pintype "bidirectional"))
    )
    (net (code "208") (name "unconnected-(U5-S11-Pad9)") (class "Default")
      (node (ref "U5") (pin "9") (pinfunction "S11_9") (pintype "bidirectional"))
    )
    (net (code "209") (name "unconnected-(U5-S12-Pad8)") (class "Default")
      (node (ref "U5") (pin "8") (pinfunction "S12_8") (pintype "bidirectional"))
    )
    (net (code "210") (name "unconnected-(U5-S13-Pad7)") (class "Default")
      (node (ref "U5") (pin "7") (pinfunction "S13_7") (pintype "bidirectional"))
    )
    (net (code "211") (name "unconnected-(U5-S14-Pad6)") (class "Default")
      (node (ref "U5") (pin "6") (pinfunction "S14_6") (pintype "bidirectional"))
    )
    (net (code "212") (name "unconnected-(U5-S15-Pad5)") (class "Default")
      (node (ref "U5") (pin "5") (pinfunction "S15_5") (pintype "bidirectional"))
    )
    (net (code "213") (name "unconnected-(U5-S16-Pad4)") (class "Default")
      (node (ref "U5") (pin "4") (pinfunction "S16_4") (pintype "bidirectional"))
    )
    (net (code "214") (name "unconnected-(U6-COL-Pad42)") (class "Default")
      (node (ref "U6") (pin "42") (pinfunction "COL_42") (pintype "output"))
    )
    (net (code "215") (name "unconnected-(U6-LED_SPEED-Pad27)") (class "Default")
      (node (ref "U6") (pin "27") (pinfunction "LED_SPEED_27") (pintype "output"))
    )
    (net (code "216") (name "unconnected-(U6-PWRDN_INTN-Pad7)") (class "Default")
      (node (ref "U6") (pin "7") (pinfunction "PWRDN_INTN_7") (pintype "bidirectional"))
    )
    (net (code "217") (name "unconnected-(U6-RXD_2-Pad45)") (class "Default")
      (node (ref "U6") (pin "45") (pinfunction "RXD_2_45") (pintype "output"))
    )
    (net (code "218") (name "unconnected-(U6-RXD_3-Pad46)") (class "Default")
      (node (ref "U6") (pin "46") (pinfunction "RXD_3_46") (pintype "output"))
    )
    (net (code "219") (name "unconnected-(U6-RX_CLK-Pad38)") (class "Default")
      (node (ref "U6") (pin "38") (pinfunction "RX_CLK_38") (pintype "output"))
    )
    (net (code "220") (name "unconnected-(U6-RX_ER-Pad41)") (class "Default")
      (node (ref "U6") (pin "41") (pinfunction "RX_ER_41") (pintype "output"))
    )
    (net (code "221") (name "unconnected-(U6-TXD_2-Pad5)") (class "Default")
      (node (ref "U6") (pin "5") (pinfunction "TXD_2_5") (pintype "input"))
    )
    (net (code "222") (name "unconnected-(U6-TXD_3-Pad6)") (class "Default")
      (node (ref "U6") (pin "6") (pinfunction "TXD_3_6") (pintype "input"))
    )
    (net (code "223") (name "unconnected-(U6-TX_CLK-Pad1)") (class "Default")
      (node (ref "U6") (pin "1") (pinfunction "TX_CLK_1") (pintype "output"))
    )
    (net (code "224") (name "unconnected-(U6-X2-Pad33)") (class "Default")
      (node (ref "U6") (pin "33") (pinfunction "X2_33") (pintype "output"))
    )
    (net (code "225") (name "~{RST}") (class "Default")
      (node (ref "JP1") (pin "6") (pinfunction "6_6") (pintype "passive"))
      (node (ref "S2") (pin "1") (pinfunction "0_1") (pintype "passive"))
      (node (ref "S2") (pin "2") (pinfunction "0_2") (pintype "passive"))
    )
  )
)
